# LCR.net
KiCad netlist of a schematic drawn in EasyEDA Pro
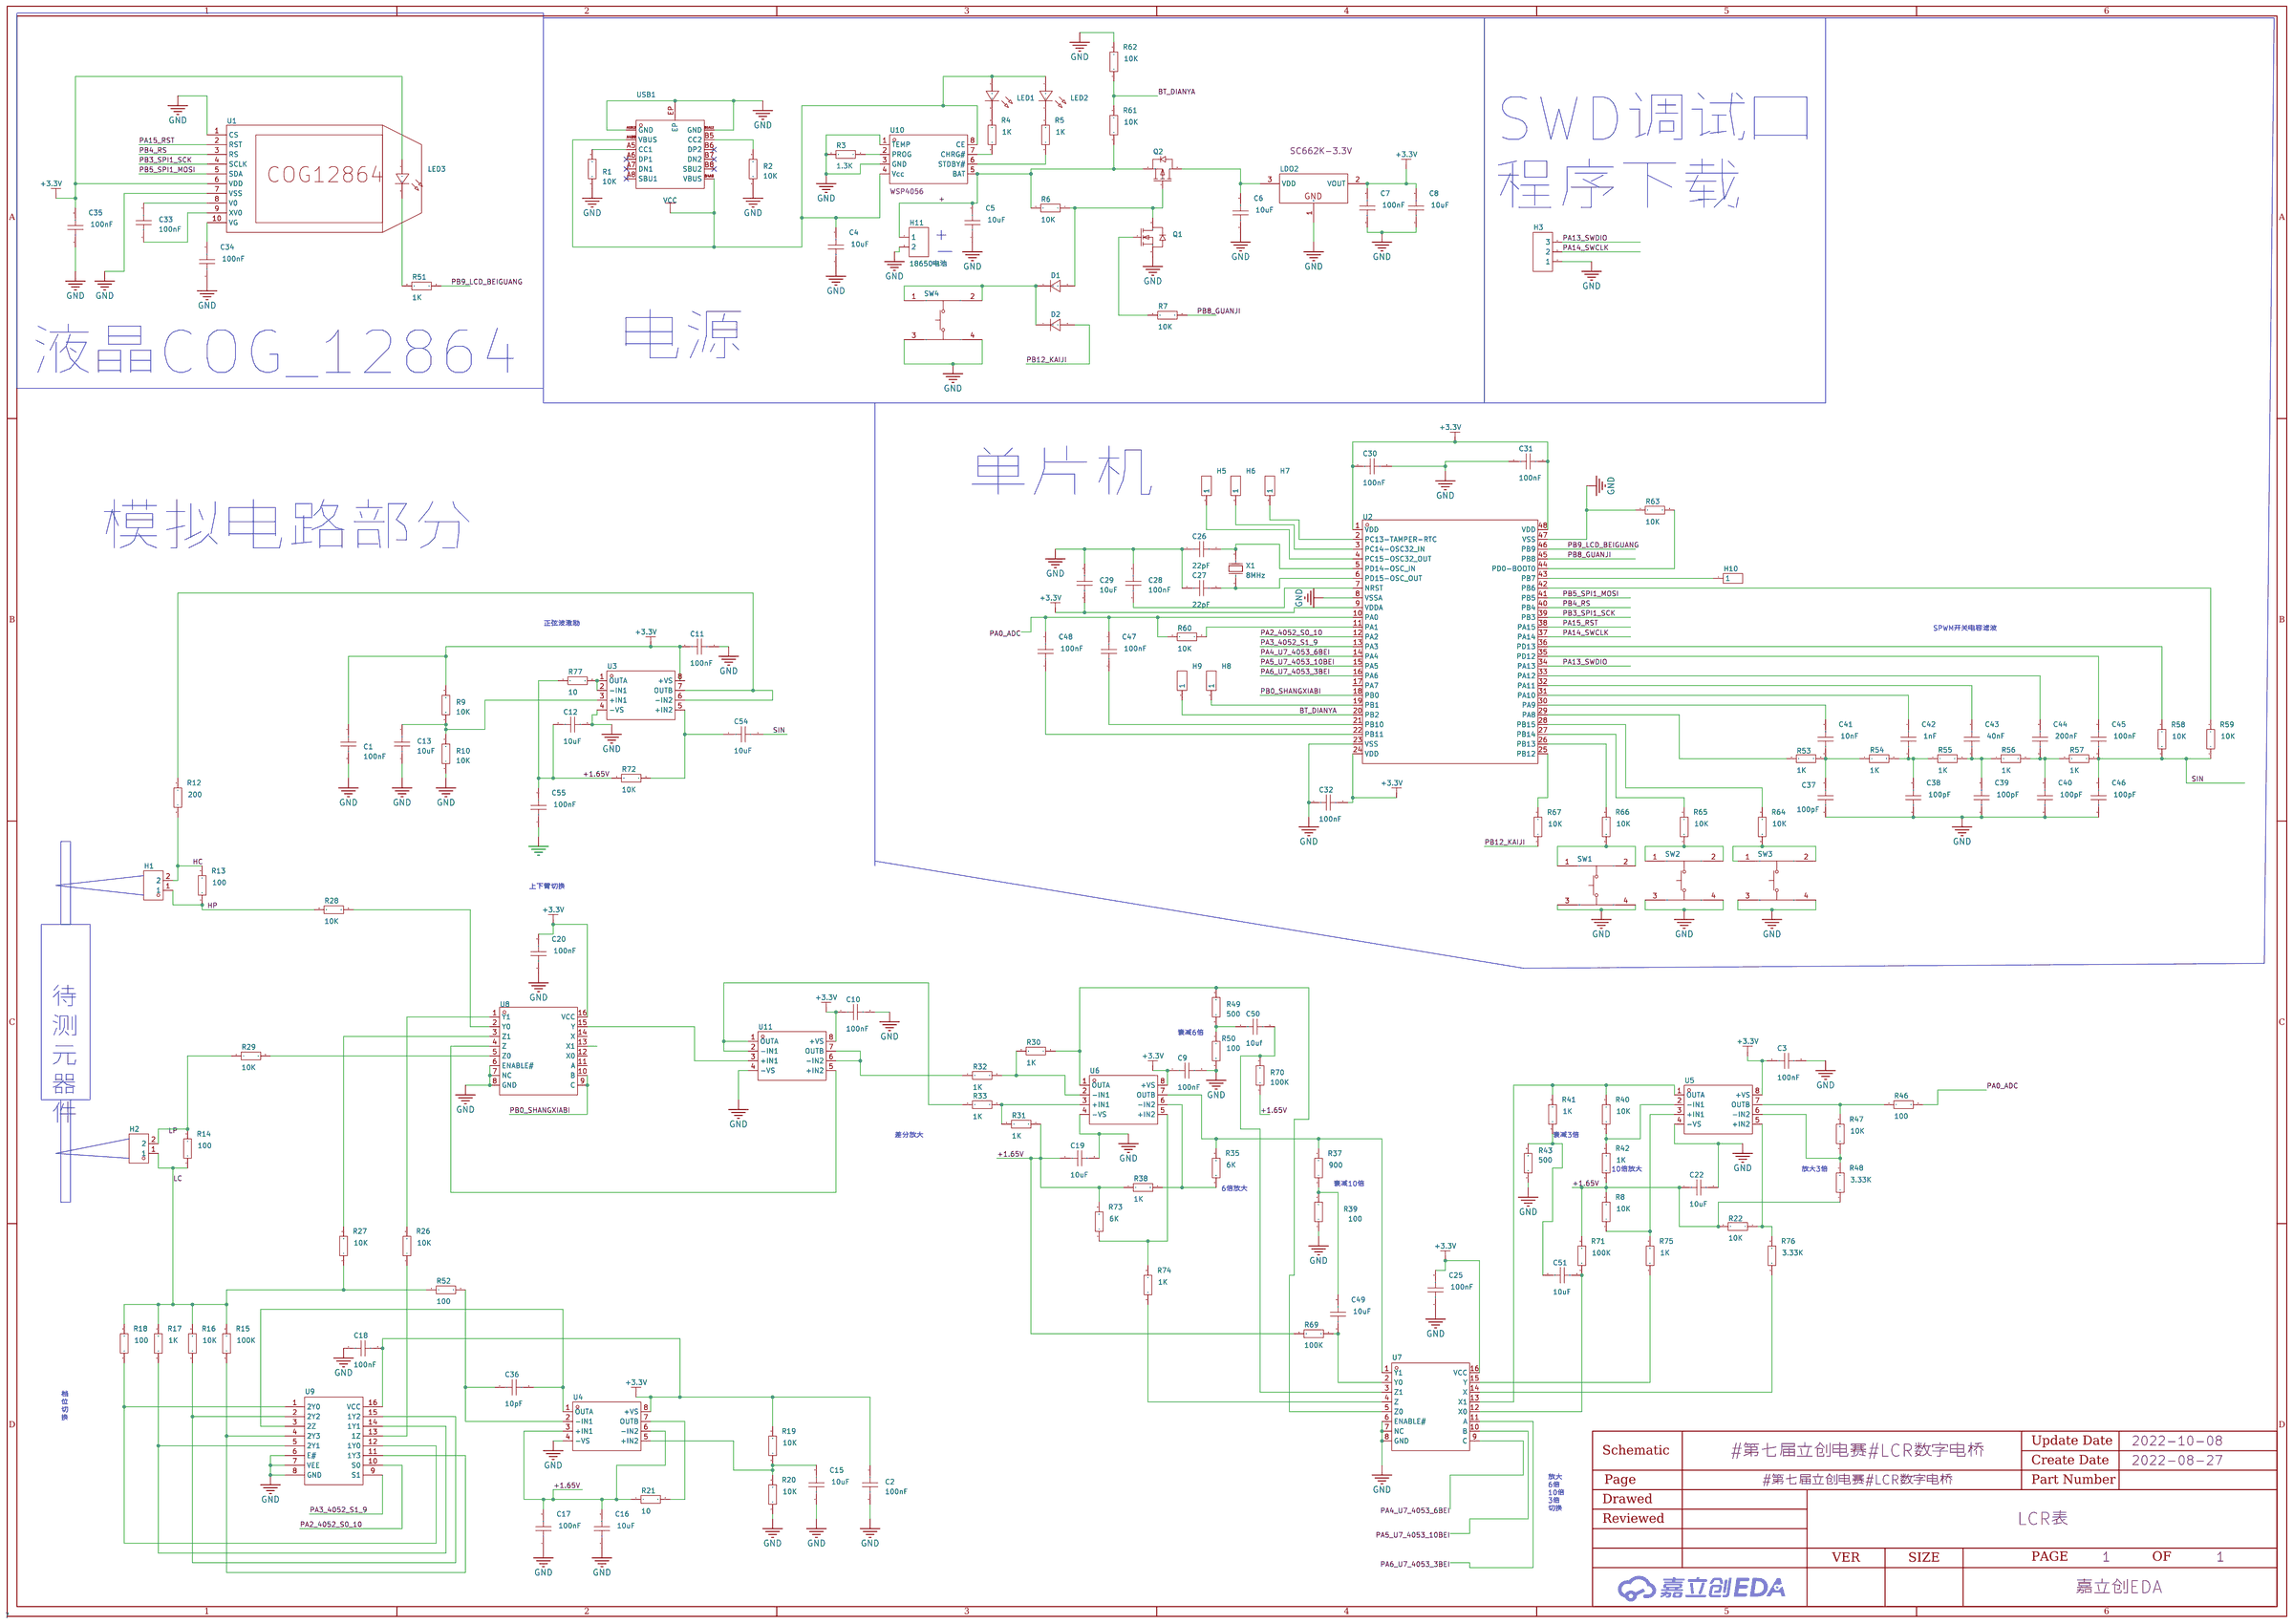
[diagram p0: schematic sheet]

(export (version "E")
  (design (tool "Eeschema 10.0.6"))
  (components
    (comp (ref "C1")
      (value "100nF")
      (footprint "easyedapro:C0603")
      (description "容值:100nF;精度:±10%;额定电压:50V;温度系数:X7R;")
      (libsource (lib "easyedapro") (part "C1210X7R475K630NT"))
    )
    (comp (ref "C2")
      (value "100nF")
      (footprint "easyedapro:C0603")
      (description "容值:100nF;精度:±10%;额定电压:50V;温度系数:X7R;")
      (libsource (lib "easyedapro") (part "C1210X7R475K630NT"))
    )
    (comp (ref "C3")
      (value "100nF")
      (footprint "easyedapro:C0603")
      (description "容值:100nF;精度:±10%;额定电压:50V;温度系数:X7R;")
      (libsource (lib "easyedapro") (part "C1210X7R475K630NT"))
    )
    (comp (ref "C4")
      (value "10uF")
      (footprint "easyedapro:C0603")
      (description "容值:100nF;精度:±10%;额定电压:50V;温度系数:X7R;")
      (libsource (lib "easyedapro") (part "C1210X7R475K630NT"))
    )
    (comp (ref "C5")
      (value "10uF")
      (footprint "easyedapro:C0603")
      (description "容值:100nF;精度:±10%;额定电压:50V;温度系数:X7R;")
      (libsource (lib "easyedapro") (part "C1210X7R475K630NT"))
    )
    (comp (ref "C6")
      (value "10uF")
      (footprint "easyedapro:C0603")
      (description "容值:100nF;精度:±10%;额定电压:50V;温度系数:X7R;")
      (libsource (lib "easyedapro") (part "C1210X7R475K630NT"))
    )
    (comp (ref "C7")
      (value "100nF")
      (footprint "easyedapro:C0603")
      (description "容值:100nF;精度:±10%;额定电压:50V;温度系数:X7R;")
      (libsource (lib "easyedapro") (part "C1210X7R475K630NT"))
    )
    (comp (ref "C8")
      (value "10uF")
      (footprint "easyedapro:C0603")
      (description "容值:100nF;精度:±10%;额定电压:50V;温度系数:X7R;")
      (libsource (lib "easyedapro") (part "C1210X7R475K630NT"))
    )
    (comp (ref "C9")
      (value "100nF")
      (footprint "easyedapro:C0603")
      (description "容值:100nF;精度:±10%;额定电压:50V;温度系数:X7R;")
      (libsource (lib "easyedapro") (part "C1210X7R475K630NT"))
    )
    (comp (ref "C10")
      (value "100nF")
      (footprint "easyedapro:C0603")
      (description "容值:100nF;精度:±10%;额定电压:50V;温度系数:X7R;")
      (libsource (lib "easyedapro") (part "C1210X7R475K630NT"))
    )
    (comp (ref "C11")
      (value "100nF")
      (footprint "easyedapro:C0603")
      (description "容值:100nF;精度:±10%;额定电压:50V;温度系数:X7R;")
      (libsource (lib "easyedapro") (part "C1210X7R475K630NT"))
    )
    (comp (ref "C12")
      (value "10uF")
      (footprint "easyedapro:C0603")
      (description "容值:100nF;精度:±10%;额定电压:50V;温度系数:X7R;")
      (libsource (lib "easyedapro") (part "C1210X7R475K630NT"))
    )
    (comp (ref "C13")
      (value "10uF")
      (footprint "easyedapro:C0603")
      (description "容值:100nF;精度:±10%;额定电压:50V;温度系数:X7R;")
      (libsource (lib "easyedapro") (part "C1210X7R475K630NT"))
    )
    (comp (ref "C15")
      (value "10uF")
      (footprint "easyedapro:C0603")
      (description "容值:100nF;精度:±10%;额定电压:50V;温度系数:X7R;")
      (libsource (lib "easyedapro") (part "C1210X7R475K630NT"))
    )
    (comp (ref "C16")
      (value "10uF")
      (footprint "easyedapro:C0603")
      (description "容值:100nF;精度:±10%;额定电压:50V;温度系数:X7R;")
      (libsource (lib "easyedapro") (part "C1210X7R475K630NT"))
    )
    (comp (ref "C17")
      (value "100nF")
      (footprint "easyedapro:C0603")
      (description "容值:100nF;精度:±10%;额定电压:50V;温度系数:X7R;")
      (libsource (lib "easyedapro") (part "C1210X7R475K630NT"))
    )
    (comp (ref "C18")
      (value "100nF")
      (footprint "easyedapro:C0603")
      (description "容值:100nF;精度:±10%;额定电压:50V;温度系数:X7R;")
      (libsource (lib "easyedapro") (part "C1210X7R475K630NT"))
    )
    (comp (ref "C19")
      (value "10uF")
      (footprint "easyedapro:C0603")
      (description "容值:100nF;精度:±10%;额定电压:50V;温度系数:X7R;")
      (libsource (lib "easyedapro") (part "C1210X7R475K630NT"))
    )
    (comp (ref "C20")
      (value "100nF")
      (footprint "easyedapro:C0603")
      (description "容值:100nF;精度:±10%;额定电压:50V;温度系数:X7R;")
      (libsource (lib "easyedapro") (part "C1210X7R475K630NT"))
    )
    (comp (ref "C22")
      (value "10uF")
      (footprint "easyedapro:C0603")
      (description "容值:100nF;精度:±10%;额定电压:50V;温度系数:X7R;")
      (libsource (lib "easyedapro") (part "C1210X7R475K630NT"))
    )
    (comp (ref "C25")
      (value "100nF")
      (footprint "easyedapro:C0603")
      (description "容值:100nF;精度:±10%;额定电压:50V;温度系数:X7R;")
      (libsource (lib "easyedapro") (part "C1210X7R475K630NT"))
    )
    (comp (ref "C26")
      (value "22pF")
      (footprint "easyedapro:C0603")
      (description "容值:100nF;精度:±10%;额定电压:50V;温度系数:X7R;")
      (libsource (lib "easyedapro") (part "C1210X7R475K630NT"))
    )
    (comp (ref "C27")
      (value "22pF")
      (footprint "easyedapro:C0603")
      (description "容值:100nF;精度:±10%;额定电压:50V;温度系数:X7R;")
      (libsource (lib "easyedapro") (part "C1210X7R475K630NT"))
    )
    (comp (ref "C28")
      (value "100nF")
      (footprint "easyedapro:C0603")
      (description "容值:100nF;精度:±10%;额定电压:50V;温度系数:X7R;")
      (libsource (lib "easyedapro") (part "C1210X7R475K630NT"))
    )
    (comp (ref "C29")
      (value "10uF")
      (footprint "easyedapro:C0603")
      (description "容值:100nF;精度:±10%;额定电压:50V;温度系数:X7R;")
      (libsource (lib "easyedapro") (part "C1210X7R475K630NT"))
    )
    (comp (ref "C30")
      (value "100nF")
      (footprint "easyedapro:C0603")
      (description "容值:100nF;精度:±10%;额定电压:50V;温度系数:X7R;")
      (libsource (lib "easyedapro") (part "C1210X7R475K630NT"))
    )
    (comp (ref "C31")
      (value "100nF")
      (footprint "easyedapro:C0603")
      (description "容值:100nF;精度:±10%;额定电压:50V;温度系数:X7R;")
      (libsource (lib "easyedapro") (part "C1210X7R475K630NT"))
    )
    (comp (ref "C32")
      (value "100nF")
      (footprint "easyedapro:C0603")
      (description "容值:100nF;精度:±10%;额定电压:50V;温度系数:X7R;")
      (libsource (lib "easyedapro") (part "C1210X7R475K630NT"))
    )
    (comp (ref "C33")
      (value "100nF")
      (footprint "easyedapro:C0603")
      (description "容值:100nF;精度:±10%;额定电压:50V;温度系数:X7R;")
      (libsource (lib "easyedapro") (part "C1210X7R475K630NT"))
    )
    (comp (ref "C34")
      (value "100nF")
      (footprint "easyedapro:C0603")
      (description "容值:100nF;精度:±10%;额定电压:50V;温度系数:X7R;")
      (libsource (lib "easyedapro") (part "C1210X7R475K630NT"))
    )
    (comp (ref "C35")
      (value "100nF")
      (footprint "easyedapro:C0603")
      (description "容值:100nF;精度:±10%;额定电压:50V;温度系数:X7R;")
      (libsource (lib "easyedapro") (part "C1210X7R475K630NT"))
    )
    (comp (ref "C36")
      (value "10pF")
      (footprint "easyedapro:C0603")
      (description "容值:100nF;精度:±10%;额定电压:50V;温度系数:X7R;")
      (libsource (lib "easyedapro") (part "C1210X7R475K630NT"))
    )
    (comp (ref "C37")
      (value "100pF")
      (footprint "easyedapro:C0603")
      (description "容值:100nF;精度:±10%;额定电压:50V;温度系数:X7R;")
      (libsource (lib "easyedapro") (part "C1210X7R475K630NT"))
    )
    (comp (ref "C38")
      (value "100pF")
      (footprint "easyedapro:C0603")
      (description "容值:100nF;精度:±10%;额定电压:50V;温度系数:X7R;")
      (libsource (lib "easyedapro") (part "C1210X7R475K630NT"))
    )
    (comp (ref "C39")
      (value "100pF")
      (footprint "easyedapro:C0603")
      (description "容值:100nF;精度:±10%;额定电压:50V;温度系数:X7R;")
      (libsource (lib "easyedapro") (part "C1210X7R475K630NT"))
    )
    (comp (ref "C40")
      (value "100pF")
      (footprint "easyedapro:C0603")
      (description "容值:100nF;精度:±10%;额定电压:50V;温度系数:X7R;")
      (libsource (lib "easyedapro") (part "C1210X7R475K630NT"))
    )
    (comp (ref "C41")
      (value "10nF")
      (footprint "easyedapro:C0603")
      (description "容值:100nF;精度:±10%;额定电压:50V;温度系数:X7R;")
      (libsource (lib "easyedapro") (part "C1210X7R475K630NT"))
    )
    (comp (ref "C42")
      (value "1nF")
      (footprint "easyedapro:C0603")
      (description "容值:100nF;精度:±10%;额定电压:50V;温度系数:X7R;")
      (libsource (lib "easyedapro") (part "C1210X7R475K630NT"))
    )
    (comp (ref "C43")
      (value "40nF")
      (footprint "easyedapro:C0603")
      (description "容值:100nF;精度:±10%;额定电压:50V;温度系数:X7R;")
      (libsource (lib "easyedapro") (part "C1210X7R475K630NT"))
    )
    (comp (ref "C44")
      (value "200nF")
      (footprint "easyedapro:C0603")
      (description "容值:100nF;精度:±10%;额定电压:50V;温度系数:X7R;")
      (libsource (lib "easyedapro") (part "C1210X7R475K630NT"))
    )
    (comp (ref "C45")
      (value "100nF")
      (footprint "easyedapro:C0603")
      (description "容值:100nF;精度:±10%;额定电压:50V;温度系数:X7R;")
      (libsource (lib "easyedapro") (part "C1210X7R475K630NT"))
    )
    (comp (ref "C46")
      (value "100pF")
      (footprint "easyedapro:C0603")
      (description "容值:100nF;精度:±10%;额定电压:50V;温度系数:X7R;")
      (libsource (lib "easyedapro") (part "C1210X7R475K630NT"))
    )
    (comp (ref "C47")
      (value "100nF")
      (footprint "easyedapro:C0603")
      (description "容值:100nF;精度:±10%;额定电压:50V;温度系数:X7R;")
      (libsource (lib "easyedapro") (part "C1210X7R475K630NT"))
    )
    (comp (ref "C48")
      (value "100nF")
      (footprint "easyedapro:C0603")
      (description "容值:100nF;精度:±10%;额定电压:50V;温度系数:X7R;")
      (libsource (lib "easyedapro") (part "C1210X7R475K630NT"))
    )
    (comp (ref "C49")
      (value "10uF")
      (footprint "easyedapro:C0603")
      (description "容值:100nF;精度:±10%;额定电压:50V;温度系数:X7R;")
      (libsource (lib "easyedapro") (part "C1210X7R475K630NT"))
    )
    (comp (ref "C50")
      (value "10uf")
      (footprint "easyedapro:C0603")
      (description "容值:100nF;精度:±10%;额定电压:50V;温度系数:X7R;")
      (libsource (lib "easyedapro") (part "C1210X7R475K630NT"))
    )
    (comp (ref "C51")
      (value "10uF")
      (footprint "easyedapro:C0603")
      (description "容值:100nF;精度:±10%;额定电压:50V;温度系数:X7R;")
      (libsource (lib "easyedapro") (part "C1210X7R475K630NT"))
    )
    (comp (ref "C54")
      (value "10uF")
      (footprint "easyedapro:C0603")
      (description "容值:100nF;精度:±10%;额定电压:50V;温度系数:X7R;")
      (libsource (lib "easyedapro") (part "C1210X7R475K630NT"))
    )
    (comp (ref "C55")
      (value "100nF")
      (footprint "easyedapro:C0603")
      (description "容值:100nF;精度:±10%;额定电压:50V;温度系数:X7R;")
      (libsource (lib "easyedapro") (part "C1210X7R475K630NT"))
    )
    (comp (ref "D1")
      (value "1N4148")
      (footprint "easyedapro:DO-35_BD2.0-L4.2-P8.20-D0.5-RD")
      (fields (field (name "Manufacturer") "GOOD-ARK(固锝)"))
      (libsource (lib "easyedapro") (part "1N4148_C406389"))
    )
    (comp (ref "D2")
      (value "1N4148")
      (footprint "easyedapro:DO-35_BD2.0-L4.2-P8.20-D0.5-RD")
      (fields (field (name "Manufacturer") "GOOD-ARK(固锝)"))
      (libsource (lib "easyedapro") (part "1N4148_C406389"))
    )
    (comp (ref "H1")
      (value "PZ254V-11-02P")
      (footprint "easyedapro:HDR-TH_2P-P2.54-V-M")
      (fields (field (name "Manufacturer") "XFCN(兴飞)"))
      (libsource (lib "easyedapro") (part "PZ254V-11-02P"))
    )
    (comp (ref "H2")
      (value "PZ254V-11-02P")
      (footprint "easyedapro:HDR-TH_2P-P2.54-V-M")
      (fields (field (name "Manufacturer") "XFCN(兴飞)"))
      (libsource (lib "easyedapro") (part "PZ254V-11-02P"))
    )
    (comp (ref "H3")
      (value "2.54-1*3P针")
      (footprint "easyedapro:HDR-TH_3P-P2.54-V-M-1")
      (fields (field (name "Manufacturer") "BOOMELE(博穆精密)"))
      (libsource (lib "easyedapro") (part "Header-Male-2.54_1x3"))
    )
    (comp (ref "H5")
      (value "~")
      (footprint "easyedapro:HDR-TH_1P-V-M_XKB_X4611WV-01I-C28D40")
      (libsource (lib "easyedapro") (part "HDR_1x1"))
    )
    (comp (ref "H6")
      (value "~")
      (footprint "easyedapro:HDR-TH_1P-V-M_XKB_X4611WV-01I-C28D40")
      (libsource (lib "easyedapro") (part "HDR_1x1"))
    )
    (comp (ref "H7")
      (value "~")
      (footprint "easyedapro:HDR-TH_1P-V-M_XKB_X4611WV-01I-C28D40")
      (libsource (lib "easyedapro") (part "HDR_1x1"))
    )
    (comp (ref "H8")
      (value "~")
      (footprint "easyedapro:HDR-TH_1P-V-M_XKB_X4611WV-01I-C28D40")
      (libsource (lib "easyedapro") (part "HDR_1x1"))
    )
    (comp (ref "H9")
      (value "~")
      (footprint "easyedapro:HDR-TH_1P-V-M_XKB_X4611WV-01I-C28D40")
      (libsource (lib "easyedapro") (part "HDR_1x1"))
    )
    (comp (ref "H10")
      (value "~")
      (footprint "easyedapro:HDR-TH_1P-V-M_XKB_X4611WV-01I-C28D40")
      (libsource (lib "easyedapro") (part "HDR_1x1"))
    )
    (comp (ref "H11")
      (value "18650电池")
      (footprint "easyedapro:HDR-TH_2P-P2.54-V-F")
      (libsource (lib "easyedapro") (part "Header-Female-2.54_1x2"))
    )
    (comp (ref "LDO2")
      (value "SC662K-3.3V")
      (footprint "easyedapro:SOT-23-3_L2.9-W1.3-P1.90-LS2.4-BR")
      (description "输出类型:固定;输出极性:正;输出通道数:1;最大输入电压:6V;输出电压:3.3V;压差:38mV@(10mA);输出电流:250mA;电源纹波抑制比(PRSS):50dB@(1kHz);")
      (fields (field (name "Manufacturer Part") "SC662K-3.3V") (field (name "Manufacturer") "FM富满"))
      (libsource (lib "easyedapro") (part "SC662K-3.3V"))
    )
    (comp (ref "LED1")
      (value "~")
      (footprint "easyedapro:LED-TH_BD3.0-P2.54-FD")
      (libsource (lib "easyedapro") (part "LED_TH-R"))
    )
    (comp (ref "LED2")
      (value "~")
      (footprint "easyedapro:LED-TH_BD3.0-P2.54-FD")
      (libsource (lib "easyedapro") (part "LED_TH-R"))
    )
    (comp (ref "LED3")
      (value "~")
      (footprint "easyedapro:LED-TH_BD3.0-P2.54-FD")
      (libsource (lib "easyedapro") (part "LED_TH-R"))
    )
    (comp (ref "Q1")
      (value "AO3400A")
      (footprint "easyedapro:SOT-23-3_L2.9-W1.3-P1.90-LS2.4-BR")
      (fields (field (name "Manufacturer") "UMW(友台半导体)"))
      (libsource (lib "easyedapro") (part "AO3400A_C347475"))
    )
    (comp (ref "Q2")
      (value "AO3401A")
      (footprint "easyedapro:SOT-23_L2.9-W1.3-P1.90-LS2.4-BR")
      (fields (field (name "Manufacturer") "UMW(友台半导体)"))
      (libsource (lib "easyedapro") (part "AO3401A_C347476"))
    )
    (comp (ref "R1")
      (value "10K")
      (footprint "easyedapro:R1206")
      (fields (field (name "Manufacturer Part") "RK73H2ETTD1002F") (field (name "Manufacturer") "KOA"))
      (libsource (lib "easyedapro") (part "电阻"))
    )
    (comp (ref "R2")
      (value "10K")
      (footprint "easyedapro:R1206")
      (fields (field (name "Manufacturer Part") "RK73H2ETTD1002F") (field (name "Manufacturer") "KOA"))
      (libsource (lib "easyedapro") (part "电阻"))
    )
    (comp (ref "R3")
      (value "1.3K")
      (footprint "easyedapro:R1206")
      (fields (field (name "Manufacturer Part") "RK73H2ETTD1002F") (field (name "Manufacturer") "KOA"))
      (libsource (lib "easyedapro") (part "电阻"))
    )
    (comp (ref "R4")
      (value "1K")
      (footprint "easyedapro:R1206")
      (fields (field (name "Manufacturer Part") "RK73H2ETTD1002F") (field (name "Manufacturer") "KOA"))
      (libsource (lib "easyedapro") (part "电阻"))
    )
    (comp (ref "R5")
      (value "1K")
      (footprint "easyedapro:R1206")
      (fields (field (name "Manufacturer Part") "RK73H2ETTD1002F") (field (name "Manufacturer") "KOA"))
      (libsource (lib "easyedapro") (part "电阻"))
    )
    (comp (ref "R6")
      (value "10K")
      (footprint "easyedapro:R1206")
      (fields (field (name "Manufacturer Part") "RK73H2ETTD1002F") (field (name "Manufacturer") "KOA"))
      (libsource (lib "easyedapro") (part "电阻"))
    )
    (comp (ref "R7")
      (value "10K")
      (footprint "easyedapro:R1206")
      (fields (field (name "Manufacturer Part") "RK73H2ETTD1002F") (field (name "Manufacturer") "KOA"))
      (libsource (lib "easyedapro") (part "电阻"))
    )
    (comp (ref "R8")
      (value "10K")
      (footprint "easyedapro:R1206")
      (fields (field (name "Manufacturer Part") "RK73H2ETTD1002F") (field (name "Manufacturer") "KOA"))
      (libsource (lib "easyedapro") (part "电阻"))
    )
    (comp (ref "R9")
      (value "10K")
      (footprint "easyedapro:R1206")
      (fields (field (name "Manufacturer Part") "RK73H2ETTD1002F") (field (name "Manufacturer") "KOA"))
      (libsource (lib "easyedapro") (part "电阻"))
    )
    (comp (ref "R10")
      (value "10K")
      (footprint "easyedapro:R1206")
      (fields (field (name "Manufacturer Part") "RK73H2ETTD1002F") (field (name "Manufacturer") "KOA"))
      (libsource (lib "easyedapro") (part "电阻"))
    )
    (comp (ref "R12")
      (value "200")
      (footprint "easyedapro:R1206")
      (fields (field (name "Manufacturer Part") "RK73H2ETTD1002F") (field (name "Manufacturer") "KOA"))
      (libsource (lib "easyedapro") (part "电阻"))
    )
    (comp (ref "R13")
      (value "100")
      (footprint "easyedapro:R1206")
      (fields (field (name "Manufacturer Part") "RK73H2ETTD1002F") (field (name "Manufacturer") "KOA"))
      (libsource (lib "easyedapro") (part "电阻"))
    )
    (comp (ref "R14")
      (value "100")
      (footprint "easyedapro:R1206")
      (fields (field (name "Manufacturer Part") "RK73H2ETTD1002F") (field (name "Manufacturer") "KOA"))
      (libsource (lib "easyedapro") (part "电阻"))
    )
    (comp (ref "R15")
      (value "100K")
      (footprint "easyedapro:R1206")
      (fields (field (name "Manufacturer Part") "RK73H2ETTD1002F") (field (name "Manufacturer") "KOA"))
      (libsource (lib "easyedapro") (part "电阻"))
    )
    (comp (ref "R16")
      (value "10K")
      (footprint "easyedapro:R1206")
      (fields (field (name "Manufacturer Part") "RK73H2ETTD1002F") (field (name "Manufacturer") "KOA"))
      (libsource (lib "easyedapro") (part "电阻"))
    )
    (comp (ref "R17")
      (value "1K")
      (footprint "easyedapro:R1206")
      (fields (field (name "Manufacturer Part") "RK73H2ETTD1002F") (field (name "Manufacturer") "KOA"))
      (libsource (lib "easyedapro") (part "电阻"))
    )
    (comp (ref "R18")
      (value "100")
      (footprint "easyedapro:R1206")
      (fields (field (name "Manufacturer Part") "RK73H2ETTD1002F") (field (name "Manufacturer") "KOA"))
      (libsource (lib "easyedapro") (part "电阻"))
    )
    (comp (ref "R19")
      (value "10K")
      (footprint "easyedapro:R1206")
      (fields (field (name "Manufacturer Part") "RK73H2ETTD1002F") (field (name "Manufacturer") "KOA"))
      (libsource (lib "easyedapro") (part "电阻"))
    )
    (comp (ref "R20")
      (value "10K")
      (footprint "easyedapro:R1206")
      (fields (field (name "Manufacturer Part") "RK73H2ETTD1002F") (field (name "Manufacturer") "KOA"))
      (libsource (lib "easyedapro") (part "电阻"))
    )
    (comp (ref "R21")
      (value "10")
      (footprint "easyedapro:R1206")
      (fields (field (name "Manufacturer Part") "RK73H2ETTD1002F") (field (name "Manufacturer") "KOA"))
      (libsource (lib "easyedapro") (part "电阻"))
    )
    (comp (ref "R22")
      (value "10K")
      (footprint "easyedapro:R1206")
      (fields (field (name "Manufacturer Part") "RK73H2ETTD1002F") (field (name "Manufacturer") "KOA"))
      (libsource (lib "easyedapro") (part "电阻"))
    )
    (comp (ref "R26")
      (value "10K")
      (footprint "easyedapro:R1206")
      (fields (field (name "Manufacturer Part") "RK73H2ETTD1002F") (field (name "Manufacturer") "KOA"))
      (libsource (lib "easyedapro") (part "电阻"))
    )
    (comp (ref "R27")
      (value "10K")
      (footprint "easyedapro:R1206")
      (fields (field (name "Manufacturer Part") "RK73H2ETTD1002F") (field (name "Manufacturer") "KOA"))
      (libsource (lib "easyedapro") (part "电阻"))
    )
    (comp (ref "R28")
      (value "10K")
      (footprint "easyedapro:R1206")
      (fields (field (name "Manufacturer Part") "RK73H2ETTD1002F") (field (name "Manufacturer") "KOA"))
      (libsource (lib "easyedapro") (part "电阻"))
    )
    (comp (ref "R29")
      (value "10K")
      (footprint "easyedapro:R1206")
      (fields (field (name "Manufacturer Part") "RK73H2ETTD1002F") (field (name "Manufacturer") "KOA"))
      (libsource (lib "easyedapro") (part "电阻"))
    )
    (comp (ref "R30")
      (value "1K")
      (footprint "easyedapro:R1206")
      (fields (field (name "Manufacturer Part") "RK73H2ETTD1002F") (field (name "Manufacturer") "KOA"))
      (libsource (lib "easyedapro") (part "电阻"))
    )
    (comp (ref "R31")
      (value "1K")
      (footprint "easyedapro:R1206")
      (fields (field (name "Manufacturer Part") "RK73H2ETTD1002F") (field (name "Manufacturer") "KOA"))
      (libsource (lib "easyedapro") (part "电阻"))
    )
    (comp (ref "R32")
      (value "1K")
      (footprint "easyedapro:R1206")
      (fields (field (name "Manufacturer Part") "RK73H2ETTD1002F") (field (name "Manufacturer") "KOA"))
      (libsource (lib "easyedapro") (part "电阻"))
    )
    (comp (ref "R33")
      (value "1K")
      (footprint "easyedapro:R1206")
      (fields (field (name "Manufacturer Part") "RK73H2ETTD1002F") (field (name "Manufacturer") "KOA"))
      (libsource (lib "easyedapro") (part "电阻"))
    )
    (comp (ref "R35")
      (value "6K")
      (footprint "easyedapro:R1206")
      (fields (field (name "Manufacturer Part") "RK73H2ETTD1002F") (field (name "Manufacturer") "KOA"))
      (libsource (lib "easyedapro") (part "电阻"))
    )
    (comp (ref "R37")
      (value "900")
      (footprint "easyedapro:R1206")
      (fields (field (name "Manufacturer Part") "RK73H2ETTD1002F") (field (name "Manufacturer") "KOA"))
      (libsource (lib "easyedapro") (part "电阻"))
    )
    (comp (ref "R38")
      (value "1K")
      (footprint "easyedapro:R1206")
      (fields (field (name "Manufacturer Part") "RK73H2ETTD1002F") (field (name "Manufacturer") "KOA"))
      (libsource (lib "easyedapro") (part "电阻"))
    )
    (comp (ref "R39")
      (value "100")
      (footprint "easyedapro:R1206")
      (fields (field (name "Manufacturer Part") "RK73H2ETTD1002F") (field (name "Manufacturer") "KOA"))
      (libsource (lib "easyedapro") (part "电阻"))
    )
    (comp (ref "R40")
      (value "10K")
      (footprint "easyedapro:R1206")
      (fields (field (name "Manufacturer Part") "RK73H2ETTD1002F") (field (name "Manufacturer") "KOA"))
      (libsource (lib "easyedapro") (part "电阻"))
    )
    (comp (ref "R41")
      (value "1K")
      (footprint "easyedapro:R1206")
      (fields (field (name "Manufacturer Part") "RK73H2ETTD1002F") (field (name "Manufacturer") "KOA"))
      (libsource (lib "easyedapro") (part "电阻"))
    )
    (comp (ref "R42")
      (value "1K")
      (footprint "easyedapro:R1206")
      (fields (field (name "Manufacturer Part") "RK73H2ETTD1002F") (field (name "Manufacturer") "KOA"))
      (libsource (lib "easyedapro") (part "电阻"))
    )
    (comp (ref "R43")
      (value "500")
      (footprint "easyedapro:R1206")
      (fields (field (name "Manufacturer Part") "RK73H2ETTD1002F") (field (name "Manufacturer") "KOA"))
      (libsource (lib "easyedapro") (part "电阻"))
    )
    (comp (ref "R46")
      (value "100")
      (footprint "easyedapro:R1206")
      (fields (field (name "Manufacturer Part") "RK73H2ETTD1002F") (field (name "Manufacturer") "KOA"))
      (libsource (lib "easyedapro") (part "电阻"))
    )
    (comp (ref "R47")
      (value "10K")
      (footprint "easyedapro:R1206")
      (fields (field (name "Manufacturer Part") "RK73H2ETTD1002F") (field (name "Manufacturer") "KOA"))
      (libsource (lib "easyedapro") (part "电阻"))
    )
    (comp (ref "R48")
      (value "3.33K")
      (footprint "easyedapro:R1206")
      (fields (field (name "Manufacturer Part") "RK73H2ETTD1002F") (field (name "Manufacturer") "KOA"))
      (libsource (lib "easyedapro") (part "电阻"))
    )
    (comp (ref "R49")
      (value "500")
      (footprint "easyedapro:R1206")
      (fields (field (name "Manufacturer Part") "RK73H2ETTD1002F") (field (name "Manufacturer") "KOA"))
      (libsource (lib "easyedapro") (part "电阻"))
    )
    (comp (ref "R50")
      (value "100")
      (footprint "easyedapro:R1206")
      (fields (field (name "Manufacturer Part") "RK73H2ETTD1002F") (field (name "Manufacturer") "KOA"))
      (libsource (lib "easyedapro") (part "电阻"))
    )
    (comp (ref "R51")
      (value "1K")
      (footprint "easyedapro:R1206")
      (fields (field (name "Manufacturer Part") "RK73H2ETTD1002F") (field (name "Manufacturer") "KOA"))
      (libsource (lib "easyedapro") (part "电阻"))
    )
    (comp (ref "R52")
      (value "100")
      (footprint "easyedapro:R1206")
      (fields (field (name "Manufacturer Part") "RK73H2ETTD1002F") (field (name "Manufacturer") "KOA"))
      (libsource (lib "easyedapro") (part "电阻"))
    )
    (comp (ref "R53")
      (value "1K")
      (footprint "easyedapro:R1206")
      (fields (field (name "Manufacturer Part") "RK73H2ETTD1002F") (field (name "Manufacturer") "KOA"))
      (libsource (lib "easyedapro") (part "电阻"))
    )
    (comp (ref "R54")
      (value "1K")
      (footprint "easyedapro:R1206")
      (fields (field (name "Manufacturer Part") "RK73H2ETTD1002F") (field (name "Manufacturer") "KOA"))
      (libsource (lib "easyedapro") (part "电阻"))
    )
    (comp (ref "R55")
      (value "1K")
      (footprint "easyedapro:R1206")
      (fields (field (name "Manufacturer Part") "RK73H2ETTD1002F") (field (name "Manufacturer") "KOA"))
      (libsource (lib "easyedapro") (part "电阻"))
    )
    (comp (ref "R56")
      (value "1K")
      (footprint "easyedapro:R1206")
      (fields (field (name "Manufacturer Part") "RK73H2ETTD1002F") (field (name "Manufacturer") "KOA"))
      (libsource (lib "easyedapro") (part "电阻"))
    )
    (comp (ref "R57")
      (value "1K")
      (footprint "easyedapro:R1206")
      (fields (field (name "Manufacturer Part") "RK73H2ETTD1002F") (field (name "Manufacturer") "KOA"))
      (libsource (lib "easyedapro") (part "电阻"))
    )
    (comp (ref "R58")
      (value "10K")
      (footprint "easyedapro:R1206")
      (fields (field (name "Manufacturer Part") "RK73H2ETTD1002F") (field (name "Manufacturer") "KOA"))
      (libsource (lib "easyedapro") (part "电阻"))
    )
    (comp (ref "R59")
      (value "10K")
      (footprint "easyedapro:R1206")
      (fields (field (name "Manufacturer Part") "RK73H2ETTD1002F") (field (name "Manufacturer") "KOA"))
      (libsource (lib "easyedapro") (part "电阻"))
    )
    (comp (ref "R60")
      (value "10K")
      (footprint "easyedapro:R1206")
      (fields (field (name "Manufacturer Part") "RK73H2ETTD1002F") (field (name "Manufacturer") "KOA"))
      (libsource (lib "easyedapro") (part "电阻"))
    )
    (comp (ref "R61")
      (value "10K")
      (footprint "easyedapro:R1206")
      (fields (field (name "Manufacturer Part") "RK73H2ETTD1002F") (field (name "Manufacturer") "KOA"))
      (libsource (lib "easyedapro") (part "电阻"))
    )
    (comp (ref "R62")
      (value "10K")
      (footprint "easyedapro:R1206")
      (fields (field (name "Manufacturer Part") "RK73H2ETTD1002F") (field (name "Manufacturer") "KOA"))
      (libsource (lib "easyedapro") (part "电阻"))
    )
    (comp (ref "R63")
      (value "10K")
      (footprint "easyedapro:R1206")
      (fields (field (name "Manufacturer Part") "RK73H2ETTD1002F") (field (name "Manufacturer") "KOA"))
      (libsource (lib "easyedapro") (part "电阻"))
    )
    (comp (ref "R64")
      (value "10K")
      (footprint "easyedapro:R1206")
      (fields (field (name "Manufacturer Part") "RK73H2ETTD1002F") (field (name "Manufacturer") "KOA"))
      (libsource (lib "easyedapro") (part "电阻"))
    )
    (comp (ref "R65")
      (value "10K")
      (footprint "easyedapro:R1206")
      (fields (field (name "Manufacturer Part") "RK73H2ETTD1002F") (field (name "Manufacturer") "KOA"))
      (libsource (lib "easyedapro") (part "电阻"))
    )
    (comp (ref "R66")
      (value "10K")
      (footprint "easyedapro:R1206")
      (fields (field (name "Manufacturer Part") "RK73H2ETTD1002F") (field (name "Manufacturer") "KOA"))
      (libsource (lib "easyedapro") (part "电阻"))
    )
    (comp (ref "R67")
      (value "10K")
      (footprint "easyedapro:R1206")
      (fields (field (name "Manufacturer Part") "RK73H2ETTD1002F") (field (name "Manufacturer") "KOA"))
      (libsource (lib "easyedapro") (part "电阻"))
    )
    (comp (ref "R69")
      (value "100K")
      (footprint "easyedapro:R1206")
      (fields (field (name "Manufacturer Part") "RK73H2ETTD1002F") (field (name "Manufacturer") "KOA"))
      (libsource (lib "easyedapro") (part "电阻"))
    )
    (comp (ref "R70")
      (value "100K")
      (footprint "easyedapro:R1206")
      (fields (field (name "Manufacturer Part") "RK73H2ETTD1002F") (field (name "Manufacturer") "KOA"))
      (libsource (lib "easyedapro") (part "电阻"))
    )
    (comp (ref "R71")
      (value "100K")
      (footprint "easyedapro:R1206")
      (fields (field (name "Manufacturer Part") "RK73H2ETTD1002F") (field (name "Manufacturer") "KOA"))
      (libsource (lib "easyedapro") (part "电阻"))
    )
    (comp (ref "R72")
      (value "10K")
      (footprint "easyedapro:R1206")
      (fields (field (name "Manufacturer Part") "RK73H2ETTD1002F") (field (name "Manufacturer") "KOA"))
      (libsource (lib "easyedapro") (part "电阻"))
    )
    (comp (ref "R73")
      (value "6K")
      (footprint "easyedapro:R1206")
      (fields (field (name "Manufacturer Part") "RK73H2ETTD1002F") (field (name "Manufacturer") "KOA"))
      (libsource (lib "easyedapro") (part "电阻"))
    )
    (comp (ref "R74")
      (value "1K")
      (footprint "easyedapro:R1206")
      (fields (field (name "Manufacturer Part") "RK73H2ETTD1002F") (field (name "Manufacturer") "KOA"))
      (libsource (lib "easyedapro") (part "电阻"))
    )
    (comp (ref "R75")
      (value "1K")
      (footprint "easyedapro:R1206")
      (fields (field (name "Manufacturer Part") "RK73H2ETTD1002F") (field (name "Manufacturer") "KOA"))
      (libsource (lib "easyedapro") (part "电阻"))
    )
    (comp (ref "R76")
      (value "3.33K")
      (footprint "easyedapro:R1206")
      (fields (field (name "Manufacturer Part") "RK73H2ETTD1002F") (field (name "Manufacturer") "KOA"))
      (libsource (lib "easyedapro") (part "电阻"))
    )
    (comp (ref "R77")
      (value "10")
      (footprint "easyedapro:R1206")
      (fields (field (name "Manufacturer Part") "RK73H2ETTD1002F") (field (name "Manufacturer") "KOA"))
      (libsource (lib "easyedapro") (part "电阻"))
    )
    (comp (ref "SW1")
      (value "TC-1109-C-B")
      (footprint "easyedapro:KEY-TH_4P-L4.5-W4.5-P3.00-LS5.8")
      (fields (field (name "Manufacturer") "XKB Connectivity(中国星坤)"))
      (libsource (lib "easyedapro") (part "TC-1109-C-B"))
    )
    (comp (ref "SW2")
      (value "TC-1109-C-B")
      (footprint "easyedapro:KEY-TH_4P-L4.5-W4.5-P3.00-LS5.8")
      (fields (field (name "Manufacturer") "XKB Connectivity(中国星坤)"))
      (libsource (lib "easyedapro") (part "TC-1109-C-B"))
    )
    (comp (ref "SW3")
      (value "TC-1109-C-B")
      (footprint "easyedapro:KEY-TH_4P-L4.5-W4.5-P3.00-LS5.8")
      (fields (field (name "Manufacturer") "XKB Connectivity(中国星坤)"))
      (libsource (lib "easyedapro") (part "TC-1109-C-B"))
    )
    (comp (ref "SW4")
      (value "TC-1109-C-B")
      (footprint "easyedapro:KEY-TH_4P-L4.5-W4.5-P3.00-LS5.8")
      (fields (field (name "Manufacturer") "XKB Connectivity(中国星坤)"))
      (libsource (lib "easyedapro") (part "TC-1109-C-B"))
    )
    (comp (ref "U1") (value "~") (libsource (lib "easyedapro") (part "COG12864")))
    (comp (ref "U2")
      (value "N32G430C8L7")
      (footprint "easyedapro:LQFP-48_L7.0-W7.0-P0.50-LS9.0-BL")
      (fields (field (name "Manufacturer") "Nations(国民技术)"))
      (libsource (lib "easyedapro") (part "N32G430C8L7"))
    )
    (comp (ref "U3")
      (value "COS722MR")
      (footprint "easyedapro:MSOP-8_L3.0-W3.0-P0.65-LS4.9-BL-1")
      (description "运放类型:低噪声运放;放大器组数:2;增益带宽积（GBP）:10MHz;压摆率（SR）:7.5 V/us;电源电压:2.1V ~ 5.5V;各通道供电电流:650uA;")
      (fields (field (name "Manufacturer") "COSINE(科山芯创)"))
      (libsource (lib "easyedapro") (part "COS722MR"))
    )
    (comp (ref "U4")
      (value "COS722MR")
      (footprint "easyedapro:MSOP-8_L3.0-W3.0-P0.65-LS4.9-BL-1")
      (description "运放类型:低噪声运放;放大器组数:2;增益带宽积（GBP）:10MHz;压摆率（SR）:7.5 V/us;电源电压:2.1V ~ 5.5V;各通道供电电流:650uA;")
      (fields (field (name "Manufacturer") "COSINE(科山芯创)"))
      (libsource (lib "easyedapro") (part "COS722MR"))
    )
    (comp (ref "U5")
      (value "COS722MR")
      (footprint "easyedapro:MSOP-8_L3.0-W3.0-P0.65-LS4.9-BL-1")
      (description "运放类型:低噪声运放;放大器组数:2;增益带宽积（GBP）:10MHz;压摆率（SR）:7.5 V/us;电源电压:2.1V ~ 5.5V;各通道供电电流:650uA;")
      (fields (field (name "Manufacturer") "COSINE(科山芯创)"))
      (libsource (lib "easyedapro") (part "COS722MR"))
    )
    (comp (ref "U6")
      (value "COS722MR")
      (footprint "easyedapro:MSOP-8_L3.0-W3.0-P0.65-LS4.9-BL-1")
      (description "运放类型:低噪声运放;放大器组数:2;增益带宽积（GBP）:10MHz;压摆率（SR）:7.5 V/us;电源电压:2.1V ~ 5.5V;各通道供电电流:650uA;")
      (fields (field (name "Manufacturer") "COSINE(科山芯创)"))
      (libsource (lib "easyedapro") (part "COS722MR"))
    )
    (comp (ref "U7")
      (value "RS2253XTSS16")
      (footprint "easyedapro:TSSOP-16_L5.0-W4.4-P0.65-LS6.4-BL")
      (description "开关电路:-;多路复用器/解复用器电路:-;导通电阻（最大值）:-;开关电压（最大值）:-;")
      (fields (field (name "Manufacturer") "RUNIC(润石)"))
      (libsource (lib "easyedapro") (part "RS2253XTSS16"))
    )
    (comp (ref "U8")
      (value "RS2253XTSS16")
      (footprint "easyedapro:TSSOP-16_L5.0-W4.4-P0.65-LS6.4-BL")
      (description "开关电路:-;多路复用器/解复用器电路:-;导通电阻（最大值）:-;开关电压（最大值）:-;")
      (fields (field (name "Manufacturer") "RUNIC(润石)"))
      (libsource (lib "easyedapro") (part "RS2253XTSS16"))
    )
    (comp (ref "U9")
      (value "74HC4052PW,118")
      (footprint "easyedapro:TSSOP-16_L5.0-W4.4-P0.65-LS6.4-BL")
      (fields (field (name "Manufacturer") "Nexperia(安世)"))
      (libsource (lib "easyedapro") (part "74HC4052PW,118"))
    )
    (comp (ref "U10")
      (value "WSP4056")
      (footprint "easyedapro:SOP-8_L5.1-W3.9-P1.27-LS6.0-BL")
      (fields (field (name "Manufacturer") "WINSOK(微硕)") (field (name "LCSC Part Name") "WSP4056"))
      (libsource (lib "easyedapro") (part "WSP4056"))
    )
    (comp (ref "U11")
      (value "COS722MR")
      (footprint "easyedapro:MSOP-8_L3.0-W3.0-P0.65-LS4.9-BL-1")
      (description "运放类型:低噪声运放;放大器组数:2;增益带宽积（GBP）:10MHz;压摆率（SR）:7.5 V/us;电源电压:2.1V ~ 5.5V;各通道供电电流:650uA;")
      (fields (field (name "Manufacturer") "COSINE(科山芯创)"))
      (libsource (lib "easyedapro") (part "COS722MR"))
    )
    (comp (ref "USB1")
      (value "TYPEC-304-ACP16")
      (footprint "easyedapro:USB-C-SMD_TYPE-C-16P-1")
      (description "连接器类型:Type-C;公母:母座;触点数量:16;端口数量:1;安装方式:卧贴;额定电流 - 电源:3A;工作温度范围:-40~+85;")
      (fields (field (name "Manufacturer") "XUNPU(讯普)"))
      (libsource (lib "easyedapro") (part "TYPEC-304-ACP16"))
    )
    (comp (ref "X1")
      (value "8MHz")
      (footprint "easyedapro:OSC-TH_L10.0-W4.5-P5.00")
      (description "晶振类型:49S晶振;频率:8MHz;频率公差:±20ppm;频率稳定度:±30ppm;负载电容:20pF;工作温度:-20~+70;")
      (fields (field (name "Manufacturer Part") "X49SD8MSD2SC") (field (name "Manufacturer") "YXC(扬兴科技)"))
      (libsource (lib "easyedapro") (part "X49SD8MSD2SC"))
    )
  )
  (nets
    (net (code "1") (name "+3.3V") (class "Default")
      (node (ref "C1") (pin "1") (pinfunction "1_1") (pintype "input"))
      (node (ref "C10") (pin "1") (pinfunction "1_1") (pintype "input"))
      (node (ref "C11") (pin "1") (pinfunction "1_1") (pintype "input"))
      (node (ref "C18") (pin "2") (pinfunction "2_2") (pintype "input"))
      (node (ref "C2") (pin "1") (pinfunction "1_1") (pintype "input"))
      (node (ref "C20") (pin "2") (pinfunction "2_2") (pintype "input"))
      (node (ref "C25") (pin "2") (pinfunction "2_2") (pintype "input"))
      (node (ref "C29") (pin "1") (pinfunction "1_1") (pintype "input"))
      (node (ref "C3") (pin "1") (pinfunction "1_1") (pintype "input"))
      (node (ref "C30") (pin "1") (pinfunction "1_1") (pintype "input"))
      (node (ref "C31") (pin "2") (pinfunction "2_2") (pintype "input"))
      (node (ref "C32") (pin "2") (pinfunction "2_2") (pintype "input"))
      (node (ref "C35") (pin "2") (pinfunction "2_2") (pintype "input"))
      (node (ref "C7") (pin "2") (pinfunction "2_2") (pintype "input"))
      (node (ref "C8") (pin "2") (pinfunction "2_2") (pintype "input"))
      (node (ref "C9") (pin "1") (pinfunction "1_1") (pintype "input"))
      (node (ref "LDO2") (pin "2") (pinfunction "VOUT_2") (pintype "input"))
      (node (ref "LED3") (pin "1") (pinfunction "C_1") (pintype "input"))
      (node (ref "R19") (pin "2") (pinfunction "2_2") (pintype "input"))
      (node (ref "R9") (pin "2") (pinfunction "2_2") (pintype "input"))
      (node (ref "U1") (pin "6") (pinfunction "VDD_6") (pintype "input"))
      (node (ref "U11") (pin "8") (pinfunction "+VS_8") (pintype "input"))
      (node (ref "U2") (pin "1") (pinfunction "VDD_1") (pintype "input"))
      (node (ref "U2") (pin "24") (pinfunction "VDD_24") (pintype "input"))
      (node (ref "U2") (pin "48") (pinfunction "VDD_48") (pintype "input"))
      (node (ref "U2") (pin "9") (pinfunction "VDDA_9") (pintype "input"))
      (node (ref "U3") (pin "8") (pinfunction "+VS_8") (pintype "input"))
      (node (ref "U4") (pin "8") (pinfunction "+VS_8") (pintype "input"))
      (node (ref "U5") (pin "8") (pinfunction "+VS_8") (pintype "input"))
      (node (ref "U6") (pin "8") (pinfunction "+VS_8") (pintype "input"))
      (node (ref "U7") (pin "16") (pinfunction "VCC_16") (pintype "input"))
      (node (ref "U8") (pin "16") (pinfunction "VCC_16") (pintype "input"))
      (node (ref "U9") (pin "16") (pinfunction "VCC_16") (pintype "input"))
    )
    (net (code "2") (name "/+") (class "Default")
      (node (ref "C5") (pin "2") (pinfunction "2_2") (pintype "input"))
      (node (ref "H11") (pin "1") (pinfunction "1_1") (pintype "input"))
      (node (ref "Q2") (pin "2") (pinfunction "S_2") (pintype "input"))
      (node (ref "R6") (pin "2") (pinfunction "2_2") (pintype "input"))
      (node (ref "R61") (pin "1") (pinfunction "1_1") (pintype "input"))
      (node (ref "U10") (pin "5") (pinfunction "BAT_5") (pintype "input"))
    )
    (net (code "3") (name "/+1.65V") (class "Default")
      (node (ref "C12") (pin "1") (pinfunction "1_1") (pintype "input"))
      (node (ref "C16") (pin "2") (pinfunction "2_2") (pintype "input"))
      (node (ref "C17") (pin "2") (pinfunction "2_2") (pintype "input"))
      (node (ref "C19") (pin "1") (pinfunction "1_1") (pintype "input"))
      (node (ref "C22") (pin "1") (pinfunction "1_1") (pintype "input"))
      (node (ref "C55") (pin "2") (pinfunction "2_2") (pintype "input"))
      (node (ref "R21") (pin "1") (pinfunction "1_1") (pintype "input"))
      (node (ref "R22") (pin "2") (pinfunction "2_2") (pintype "input"))
      (node (ref "R31") (pin "1") (pinfunction "1_1") (pintype "input"))
      (node (ref "R38") (pin "1") (pinfunction "1_1") (pintype "input"))
      (node (ref "R42") (pin "1") (pinfunction "1_1") (pintype "input"))
      (node (ref "R48") (pin "1") (pinfunction "1_1") (pintype "input"))
      (node (ref "R69") (pin "1") (pinfunction "1_1") (pintype "input"))
      (node (ref "R70") (pin "1") (pinfunction "1_1") (pintype "input"))
      (node (ref "R71") (pin "2") (pinfunction "2_2") (pintype "input"))
      (node (ref "R72") (pin "1") (pinfunction "1_1") (pintype "input"))
      (node (ref "R73") (pin "2") (pinfunction "2_2") (pintype "input"))
      (node (ref "R77") (pin "1") (pinfunction "1_1") (pintype "input"))
      (node (ref "R8") (pin "2") (pinfunction "2_2") (pintype "input"))
      (node (ref "U4") (pin "3") (pinfunction "+IN1_3") (pintype "input"))
      (node (ref "U4") (pin "6") (pinfunction "-IN2_6") (pintype "input"))
    )
    (net (code "4") (name "/BT_DIANYA") (class "Default")
      (node (ref "H9") (pin "1") (pinfunction "1_1") (pintype "unspecified"))
      (node (ref "R61") (pin "2") (pinfunction "2_2") (pintype "input"))
      (node (ref "R62") (pin "1") (pinfunction "1_1") (pintype "input"))
      (node (ref "U2") (pin "20") (pinfunction "PB2_20") (pintype "input"))
    )
    (net (code "5") (name "/HC") (class "Default")
      (node (ref "H1") (pin "2") (pinfunction "2_2") (pintype "input"))
      (node (ref "R12") (pin "1") (pinfunction "1_1") (pintype "input"))
      (node (ref "R13") (pin "2") (pinfunction "2_2") (pintype "input"))
    )
    (net (code "6") (name "/HP") (class "Default")
      (node (ref "H1") (pin "1") (pinfunction "1_1") (pintype "input"))
      (node (ref "R13") (pin "1") (pinfunction "1_1") (pintype "input"))
      (node (ref "R28") (pin "1") (pinfunction "1_1") (pintype "input"))
    )
    (net (code "7") (name "/LC") (class "Default")
      (node (ref "H2") (pin "1") (pinfunction "1_1") (pintype "input"))
      (node (ref "R14") (pin "1") (pinfunction "1_1") (pintype "input"))
      (node (ref "R15") (pin "2") (pinfunction "2_2") (pintype "input"))
      (node (ref "R16") (pin "2") (pinfunction "2_2") (pintype "input"))
      (node (ref "R17") (pin "2") (pinfunction "2_2") (pintype "input"))
      (node (ref "R18") (pin "2") (pinfunction "2_2") (pintype "input"))
      (node (ref "R27") (pin "1") (pinfunction "1_1") (pintype "input"))
      (node (ref "R52") (pin "1") (pinfunction "1_1") (pintype "input"))
    )
    (net (code "8") (name "/LP") (class "Default")
      (node (ref "H2") (pin "2") (pinfunction "2_2") (pintype "input"))
      (node (ref "R14") (pin "2") (pinfunction "2_2") (pintype "input"))
      (node (ref "R29") (pin "1") (pinfunction "1_1") (pintype "input"))
    )
    (net (code "9") (name "/PA0_ADC") (class "Default")
      (node (ref "C47") (pin "2") (pinfunction "2_2") (pintype "input"))
      (node (ref "C48") (pin "2") (pinfunction "2_2") (pintype "input"))
      (node (ref "R46") (pin "2") (pinfunction "2_2") (pintype "input"))
      (node (ref "R60") (pin "1") (pinfunction "1_1") (pintype "input"))
      (node (ref "U2") (pin "10") (pinfunction "PA0_10") (pintype "input"))
    )
    (net (code "10") (name "/PA2_4052_S0_10") (class "Default")
      (node (ref "U2") (pin "12") (pinfunction "PA2_12") (pintype "input"))
      (node (ref "U9") (pin "10") (pinfunction "S0_10") (pintype "input"))
    )
    (net (code "11") (name "/PA3_4052_S1_9") (class "Default")
      (node (ref "U2") (pin "13") (pinfunction "PA3_13") (pintype "input"))
      (node (ref "U9") (pin "9") (pinfunction "S1_9") (pintype "input"))
    )
    (net (code "12") (name "/PA4_U7_4053_6BEI") (class "Default")
      (node (ref "U2") (pin "14") (pinfunction "PA4_14") (pintype "input"))
      (node (ref "U7") (pin "9") (pinfunction "C_9") (pintype "input"))
    )
    (net (code "13") (name "/PA5_U7_4053_10BEI") (class "Default")
      (node (ref "U2") (pin "15") (pinfunction "PA5_15") (pintype "input"))
      (node (ref "U7") (pin "10") (pinfunction "B_10") (pintype "input"))
    )
    (net (code "14") (name "/PA6_U7_4053_3BEI") (class "Default")
      (node (ref "U2") (pin "16") (pinfunction "PA6_16") (pintype "input"))
      (node (ref "U7") (pin "11") (pinfunction "A_11") (pintype "input"))
    )
    (net (code "15") (name "/PA13_SWDIO") (class "Default")
      (node (ref "H3") (pin "3") (pinfunction "3_3") (pintype "input"))
      (node (ref "U2") (pin "34") (pinfunction "PA13_34") (pintype "input"))
    )
    (net (code "16") (name "/PA14_SWCLK") (class "Default")
      (node (ref "H3") (pin "2") (pinfunction "2_2") (pintype "input"))
      (node (ref "U2") (pin "37") (pinfunction "PA14_37") (pintype "input"))
    )
    (net (code "17") (name "/PA15_RST") (class "Default")
      (node (ref "U1") (pin "2") (pinfunction "RST_2") (pintype "input"))
      (node (ref "U2") (pin "38") (pinfunction "PA15_38") (pintype "input"))
    )
    (net (code "18") (name "/PB0_SHANGXIABI") (class "Default")
      (node (ref "U2") (pin "18") (pinfunction "PB0_18") (pintype "input"))
      (node (ref "U8") (pin "10") (pinfunction "B_10") (pintype "input"))
      (node (ref "U8") (pin "9") (pinfunction "C_9") (pintype "input"))
    )
    (net (code "19") (name "/PB3_SPI1_SCK") (class "Default")
      (node (ref "U1") (pin "4") (pinfunction "SCLK_4") (pintype "input"))
      (node (ref "U2") (pin "39") (pinfunction "PB3_39") (pintype "input"))
    )
    (net (code "20") (name "/PB4_RS") (class "Default")
      (node (ref "U1") (pin "3") (pinfunction "RS_3") (pintype "input"))
      (node (ref "U2") (pin "40") (pinfunction "PB4_40") (pintype "input"))
    )
    (net (code "21") (name "/PB5_SPI1_MOSI") (class "Default")
      (node (ref "U1") (pin "5") (pinfunction "SDA_5") (pintype "input"))
      (node (ref "U2") (pin "41") (pinfunction "PB5_41") (pintype "input"))
    )
    (net (code "22") (name "/PB8_GUANJI") (class "Default")
      (node (ref "R7") (pin "1") (pinfunction "1_1") (pintype "input"))
      (node (ref "U2") (pin "45") (pinfunction "PB8_45") (pintype "input"))
    )
    (net (code "23") (name "/PB9_LCD_BEIGUANG") (class "Default")
      (node (ref "R51") (pin "2") (pinfunction "2_2") (pintype "input"))
      (node (ref "U2") (pin "46") (pinfunction "PB9_46") (pintype "input"))
    )
    (net (code "24") (name "/PB12_KAIJI") (class "Default")
      (node (ref "D2") (pin "2") (pinfunction "A_2") (pintype "input"))
      (node (ref "R67") (pin "1") (pinfunction "1_1") (pintype "input"))
    )
    (net (code "25") (name "/SIN") (class "Default")
      (node (ref "C45") (pin "1") (pinfunction "1_1") (pintype "input"))
      (node (ref "C46") (pin "2") (pinfunction "2_2") (pintype "input"))
      (node (ref "C54") (pin "2") (pinfunction "2_2") (pintype "input"))
      (node (ref "R57") (pin "2") (pinfunction "2_2") (pintype "input"))
      (node (ref "R58") (pin "1") (pinfunction "1_1") (pintype "input"))
      (node (ref "R59") (pin "1") (pinfunction "1_1") (pintype "input"))
    )
    (net (code "26") (name "GND") (class "Default")
      (node (ref "C1") (pin "2") (pinfunction "2_2") (pintype "input"))
      (node (ref "C10") (pin "2") (pinfunction "2_2") (pintype "input"))
      (node (ref "C11") (pin "2") (pinfunction "2_2") (pintype "input"))
      (node (ref "C12") (pin "2") (pinfunction "2_2") (pintype "input"))
      (node (ref "C13") (pin "1") (pinfunction "1_1") (pintype "input"))
      (node (ref "C15") (pin "1") (pinfunction "1_1") (pintype "input"))
      (node (ref "C16") (pin "1") (pinfunction "1_1") (pintype "input"))
      (node (ref "C17") (pin "1") (pinfunction "1_1") (pintype "input"))
      (node (ref "C18") (pin "1") (pinfunction "1_1") (pintype "input"))
      (node (ref "C19") (pin "2") (pinfunction "2_2") (pintype "input"))
      (node (ref "C2") (pin "2") (pinfunction "2_2") (pintype "input"))
      (node (ref "C20") (pin "1") (pinfunction "1_1") (pintype "input"))
      (node (ref "C22") (pin "2") (pinfunction "2_2") (pintype "input"))
      (node (ref "C25") (pin "1") (pinfunction "1_1") (pintype "input"))
      (node (ref "C26") (pin "1") (pinfunction "1_1") (pintype "input"))
      (node (ref "C27") (pin "1") (pinfunction "1_1") (pintype "input"))
      (node (ref "C28") (pin "2") (pinfunction "2_2") (pintype "input"))
      (node (ref "C29") (pin "2") (pinfunction "2_2") (pintype "input"))
      (node (ref "C3") (pin "2") (pinfunction "2_2") (pintype "input"))
      (node (ref "C30") (pin "2") (pinfunction "2_2") (pintype "input"))
      (node (ref "C31") (pin "1") (pinfunction "1_1") (pintype "input"))
      (node (ref "C32") (pin "1") (pinfunction "1_1") (pintype "input"))
      (node (ref "C34") (pin "1") (pinfunction "1_1") (pintype "input"))
      (node (ref "C35") (pin "1") (pinfunction "1_1") (pintype "input"))
      (node (ref "C37") (pin "1") (pinfunction "1_1") (pintype "input"))
      (node (ref "C38") (pin "1") (pinfunction "1_1") (pintype "input"))
      (node (ref "C39") (pin "1") (pinfunction "1_1") (pintype "input"))
      (node (ref "C4") (pin "1") (pinfunction "1_1") (pintype "input"))
      (node (ref "C40") (pin "1") (pinfunction "1_1") (pintype "input"))
      (node (ref "C46") (pin "1") (pinfunction "1_1") (pintype "input"))
      (node (ref "C5") (pin "1") (pinfunction "1_1") (pintype "input"))
      (node (ref "C55") (pin "1") (pinfunction "1_1") (pintype "input"))
      (node (ref "C6") (pin "1") (pinfunction "1_1") (pintype "input"))
      (node (ref "C7") (pin "1") (pinfunction "1_1") (pintype "input"))
      (node (ref "C8") (pin "1") (pinfunction "1_1") (pintype "input"))
      (node (ref "C9") (pin "2") (pinfunction "2_2") (pintype "input"))
      (node (ref "H11") (pin "2") (pinfunction "2_2") (pintype "input"))
      (node (ref "H3") (pin "1") (pinfunction "1_1") (pintype "input"))
      (node (ref "LDO2") (pin "1") (pinfunction "GND_1") (pintype "input"))
      (node (ref "Q1") (pin "2") (pinfunction "S_2") (pintype "input"))
      (node (ref "R1") (pin "2") (pinfunction "2_2") (pintype "input"))
      (node (ref "R10") (pin "1") (pinfunction "1_1") (pintype "input"))
      (node (ref "R2") (pin "1") (pinfunction "1_1") (pintype "input"))
      (node (ref "R20") (pin "1") (pinfunction "1_1") (pintype "input"))
      (node (ref "R3") (pin "1") (pinfunction "1_1") (pintype "input"))
      (node (ref "R39") (pin "1") (pinfunction "1_1") (pintype "input"))
      (node (ref "R43") (pin "1") (pinfunction "1_1") (pintype "input"))
      (node (ref "R50") (pin "2") (pinfunction "2_2") (pintype "input"))
      (node (ref "R62") (pin "2") (pinfunction "2_2") (pintype "input"))
      (node (ref "R63") (pin "1") (pinfunction "1_1") (pintype "input"))
      (node (ref "SW1") (pin "3") (pinfunction "3_3") (pintype "input"))
      (node (ref "SW1") (pin "4") (pinfunction "4_4") (pintype "input"))
      (node (ref "SW2") (pin "3") (pinfunction "3_3") (pintype "input"))
      (node (ref "SW2") (pin "4") (pinfunction "4_4") (pintype "input"))
      (node (ref "SW3") (pin "3") (pinfunction "3_3") (pintype "input"))
      (node (ref "SW3") (pin "4") (pinfunction "4_4") (pintype "input"))
      (node (ref "SW4") (pin "3") (pinfunction "3_3") (pintype "input"))
      (node (ref "SW4") (pin "4") (pinfunction "4_4") (pintype "input"))
      (node (ref "U1") (pin "1") (pinfunction "CS_1") (pintype "input"))
      (node (ref "U1") (pin "7") (pinfunction "VSS_7") (pintype "input"))
      (node (ref "U10") (pin "1") (pinfunction "TEMP_1") (pintype "input"))
      (node (ref "U10") (pin "3") (pinfunction "GND_3") (pintype "input"))
      (node (ref "U11") (pin "4") (pinfunction "-VS_4") (pintype "input"))
      (node (ref "U2") (pin "23") (pinfunction "VSS_23") (pintype "input"))
      (node (ref "U2") (pin "47") (pinfunction "VSS_47") (pintype "input"))
      (node (ref "U2") (pin "8") (pinfunction "VSSA_8") (pintype "input"))
      (node (ref "U3") (pin "4") (pinfunction "-VS_4") (pintype "input"))
      (node (ref "U4") (pin "4") (pinfunction "-VS_4") (pintype "input"))
      (node (ref "U5") (pin "4") (pinfunction "-VS_4") (pintype "input"))
      (node (ref "U6") (pin "4") (pinfunction "-VS_4") (pintype "input"))
      (node (ref "U7") (pin "6") (pinfunction "ENABLE#_6") (pintype "input"))
      (node (ref "U7") (pin "7") (pinfunction "NC_7") (pintype "input"))
      (node (ref "U7") (pin "8") (pinfunction "GND_8") (pintype "input"))
      (node (ref "U8") (pin "6") (pinfunction "ENABLE#_6") (pintype "input"))
      (node (ref "U8") (pin "7") (pinfunction "NC_7") (pintype "input"))
      (node (ref "U8") (pin "8") (pinfunction "GND_8") (pintype "input"))
      (node (ref "U9") (pin "6") (pinfunction "E#_6") (pintype "input"))
      (node (ref "U9") (pin "7") (pinfunction "VEE_7") (pintype "input"))
      (node (ref "U9") (pin "8") (pinfunction "GND_8") (pintype "input"))
      (node (ref "USB1") (pin "A1B12") (pinfunction "GND_A1B12") (pintype "input"))
      (node (ref "USB1") (pin "B1A12") (pinfunction "GND_B1A12") (pintype "input"))
      (node (ref "USB1") (pin "EP") (pinfunction "EP_EP") (pintype "input"))
    )
    (net (code "27") (name "Net-(C37-Pad2)") (class "Default")
      (node (ref "C37") (pin "2") (pinfunction "2_2") (pintype "input"))
      (node (ref "C41") (pin "1") (pinfunction "1_1") (pintype "input"))
      (node (ref "R53") (pin "2") (pinfunction "2_2") (pintype "input"))
      (node (ref "R54") (pin "1") (pinfunction "1_1") (pintype "input"))
    )
    (net (code "28") (name "Net-(C38-Pad2)") (class "Default")
      (node (ref "C38") (pin "2") (pinfunction "2_2") (pintype "input"))
      (node (ref "C42") (pin "1") (pinfunction "1_1") (pintype "input"))
      (node (ref "R54") (pin "2") (pinfunction "2_2") (pintype "input"))
      (node (ref "R55") (pin "1") (pinfunction "1_1") (pintype "input"))
    )
    (net (code "29") (name "Net-(C39-Pad2)") (class "Default")
      (node (ref "C39") (pin "2") (pinfunction "2_2") (pintype "input"))
      (node (ref "C43") (pin "1") (pinfunction "1_1") (pintype "input"))
      (node (ref "R55") (pin "2") (pinfunction "2_2") (pintype "input"))
      (node (ref "R56") (pin "1") (pinfunction "1_1") (pintype "input"))
    )
    (net (code "30") (name "Net-(C40-Pad2)") (class "Default")
      (node (ref "C40") (pin "2") (pinfunction "2_2") (pintype "input"))
      (node (ref "C44") (pin "1") (pinfunction "1_1") (pintype "input"))
      (node (ref "R56") (pin "2") (pinfunction "2_2") (pintype "input"))
      (node (ref "R57") (pin "1") (pinfunction "1_1") (pintype "input"))
    )
    (net (code "31") (name "Net-(C49-Pad2)") (class "Default")
      (node (ref "C49") (pin "2") (pinfunction "2_2") (pintype "input"))
      (node (ref "R37") (pin "1") (pinfunction "1_1") (pintype "input"))
      (node (ref "R39") (pin "2") (pinfunction "2_2") (pintype "input"))
    )
    (net (code "32") (name "Net-(C50-Pad2)") (class "Default")
      (node (ref "C50") (pin "2") (pinfunction "2_2") (pintype "input"))
      (node (ref "R49") (pin "1") (pinfunction "1_1") (pintype "input"))
      (node (ref "R50") (pin "1") (pinfunction "1_1") (pintype "input"))
    )
    (net (code "33") (name "Net-(C51-Pad1)") (class "Default")
      (node (ref "C51") (pin "1") (pinfunction "1_1") (pintype "input"))
      (node (ref "R41") (pin "1") (pinfunction "1_1") (pintype "input"))
      (node (ref "R43") (pin "2") (pinfunction "2_2") (pintype "input"))
    )
    (net (code "34") (name "Net-(D1-A)") (class "Default")
      (node (ref "D1") (pin "2") (pinfunction "A_2") (pintype "input"))
      (node (ref "Q1") (pin "3") (pinfunction "D_3") (pintype "input"))
      (node (ref "Q2") (pin "1") (pinfunction "G_1") (pintype "input"))
      (node (ref "R6") (pin "1") (pinfunction "1_1") (pintype "input"))
    )
    (net (code "35") (name "Net-(D1-C)") (class "Default")
      (node (ref "D1") (pin "1") (pinfunction "C_1") (pintype "input"))
      (node (ref "D2") (pin "1") (pinfunction "C_1") (pintype "input"))
      (node (ref "SW4") (pin "1") (pinfunction "1_1") (pintype "input"))
      (node (ref "SW4") (pin "2") (pinfunction "2_2") (pintype "input"))
    )
    (net (code "36") (name "Net-(LDO2-VDD)") (class "Default")
      (node (ref "C6") (pin "2") (pinfunction "2_2") (pintype "input"))
      (node (ref "LDO2") (pin "3") (pinfunction "VDD_3") (pintype "input"))
      (node (ref "Q2") (pin "3") (pinfunction "D_3") (pintype "input"))
    )
    (net (code "37") (name "Net-(LED1-A)") (class "Default")
      (node (ref "LED1") (pin "2") (pinfunction "A_2") (pintype "input"))
      (node (ref "R4") (pin "2") (pinfunction "2_2") (pintype "input"))
    )
    (net (code "38") (name "Net-(LED2-A)") (class "Default")
      (node (ref "LED2") (pin "2") (pinfunction "A_2") (pintype "input"))
      (node (ref "R5") (pin "2") (pinfunction "2_2") (pintype "input"))
    )
    (net (code "39") (name "Net-(LED3-A)") (class "Default")
      (node (ref "LED3") (pin "2") (pinfunction "A_2") (pintype "input"))
      (node (ref "R51") (pin "1") (pinfunction "1_1") (pintype "input"))
    )
    (net (code "40") (name "Net-(Q1-G)") (class "Default")
      (node (ref "Q1") (pin "1") (pinfunction "G_1") (pintype "input"))
      (node (ref "R7") (pin "2") (pinfunction "2_2") (pintype "input"))
    )
    (net (code "41") (name "Net-(R64-Pad1)") (class "Default")
      (node (ref "R64") (pin "1") (pinfunction "1_1") (pintype "input"))
      (node (ref "SW3") (pin "1") (pinfunction "1_1") (pintype "input"))
      (node (ref "SW3") (pin "2") (pinfunction "2_2") (pintype "input"))
    )
    (net (code "42") (name "Net-(R65-Pad1)") (class "Default")
      (node (ref "R65") (pin "1") (pinfunction "1_1") (pintype "input"))
      (node (ref "SW2") (pin "1") (pinfunction "1_1") (pintype "input"))
      (node (ref "SW2") (pin "2") (pinfunction "2_2") (pintype "input"))
    )
    (net (code "43") (name "Net-(R66-Pad1)") (class "Default")
      (node (ref "R66") (pin "1") (pinfunction "1_1") (pintype "input"))
      (node (ref "SW1") (pin "1") (pinfunction "1_1") (pintype "input"))
      (node (ref "SW1") (pin "2") (pinfunction "2_2") (pintype "input"))
    )
    (net (code "44") (name "Net-(U1-V0)") (class "Default")
      (node (ref "C33") (pin "2") (pinfunction "2_2") (pintype "input"))
      (node (ref "U1") (pin "8") (pinfunction "V0_8") (pintype "input"))
    )
    (net (code "45") (name "Net-(U1-VG)") (class "Default")
      (node (ref "C34") (pin "2") (pinfunction "2_2") (pintype "input"))
      (node (ref "U1") (pin "10") (pinfunction "VG_10") (pintype "input"))
    )
    (net (code "46") (name "Net-(U1-XV0)") (class "Default")
      (node (ref "C33") (pin "1") (pinfunction "1_1") (pintype "input"))
      (node (ref "U1") (pin "9") (pinfunction "XV0_9") (pintype "input"))
    )
    (net (code "47") (name "Net-(U2-NRST)") (class "Default")
      (node (ref "C28") (pin "1") (pinfunction "1_1") (pintype "input"))
      (node (ref "U2") (pin "7") (pinfunction "NRST_7") (pintype "input"))
    )
    (net (code "48") (name "Net-(U2-PA1)") (class "Default")
      (node (ref "R60") (pin "2") (pinfunction "2_2") (pintype "input"))
      (node (ref "U2") (pin "11") (pinfunction "PA1_11") (pintype "input"))
    )
    (net (code "49") (name "Net-(U2-PA8)") (class "Default")
      (node (ref "R53") (pin "1") (pinfunction "1_1") (pintype "input"))
      (node (ref "U2") (pin "29") (pinfunction "PA8_29") (pintype "input"))
    )
    (net (code "50") (name "Net-(U2-PA9)") (class "Default")
      (node (ref "C41") (pin "2") (pinfunction "2_2") (pintype "input"))
      (node (ref "U2") (pin "30") (pinfunction "PA9_30") (pintype "input"))
    )
    (net (code "51") (name "Net-(U2-PA10)") (class "Default")
      (node (ref "C42") (pin "2") (pinfunction "2_2") (pintype "input"))
      (node (ref "U2") (pin "31") (pinfunction "PA10_31") (pintype "input"))
    )
    (net (code "52") (name "Net-(U2-PA11)") (class "Default")
      (node (ref "C43") (pin "2") (pinfunction "2_2") (pintype "input"))
      (node (ref "U2") (pin "32") (pinfunction "PA11_32") (pintype "input"))
    )
    (net (code "53") (name "Net-(U2-PA12)") (class "Default")
      (node (ref "C44") (pin "2") (pinfunction "2_2") (pintype "input"))
      (node (ref "U2") (pin "33") (pinfunction "PA12_33") (pintype "input"))
    )
    (net (code "54") (name "Net-(U2-PB1)") (class "Default")
      (node (ref "H8") (pin "1") (pinfunction "1_1") (pintype "unspecified"))
      (node (ref "U2") (pin "19") (pinfunction "PB1_19") (pintype "input"))
    )
    (net (code "55") (name "Net-(U2-PB6)") (class "Default")
      (node (ref "R59") (pin "2") (pinfunction "2_2") (pintype "input"))
      (node (ref "U2") (pin "42") (pinfunction "PB6_42") (pintype "input"))
    )
    (net (code "56") (name "Net-(U2-PB7)") (class "Default")
      (node (ref "H10") (pin "1") (pinfunction "1_1") (pintype "unspecified"))
      (node (ref "U2") (pin "43") (pinfunction "PB7_43") (pintype "input"))
    )
    (net (code "57") (name "Net-(U2-PB10)") (class "Default")
      (node (ref "C47") (pin "1") (pinfunction "1_1") (pintype "input"))
      (node (ref "U2") (pin "21") (pinfunction "PB10_21") (pintype "input"))
    )
    (net (code "58") (name "Net-(U2-PB11)") (class "Default")
      (node (ref "C48") (pin "1") (pinfunction "1_1") (pintype "input"))
      (node (ref "U2") (pin "22") (pinfunction "PB11_22") (pintype "input"))
    )
    (net (code "59") (name "Net-(U2-PB12)") (class "Default")
      (node (ref "R67") (pin "2") (pinfunction "2_2") (pintype "input"))
      (node (ref "U2") (pin "25") (pinfunction "PB12_25") (pintype "input"))
    )
    (net (code "60") (name "Net-(U2-PB13)") (class "Default")
      (node (ref "R66") (pin "2") (pinfunction "2_2") (pintype "input"))
      (node (ref "U2") (pin "26") (pinfunction "PB13_26") (pintype "input"))
    )
    (net (code "61") (name "Net-(U2-PB14)") (class "Default")
      (node (ref "R65") (pin "2") (pinfunction "2_2") (pintype "input"))
      (node (ref "U2") (pin "27") (pinfunction "PB14_27") (pintype "input"))
    )
    (net (code "62") (name "Net-(U2-PB15)") (class "Default")
      (node (ref "R64") (pin "2") (pinfunction "2_2") (pintype "input"))
      (node (ref "U2") (pin "28") (pinfunction "PB15_28") (pintype "input"))
    )
    (net (code "63") (name "Net-(U2-PC13-TAMPER-RTC)") (class "Default")
      (node (ref "H7") (pin "1") (pinfunction "1_1") (pintype "unspecified"))
      (node (ref "U2") (pin "2") (pinfunction "PC13-TAMPER-RTC_2") (pintype "input"))
    )
    (net (code "64") (name "Net-(U2-PC14-OSC32_IN)") (class "Default")
      (node (ref "H6") (pin "1") (pinfunction "1_1") (pintype "unspecified"))
      (node (ref "U2") (pin "3") (pinfunction "PC14-OSC32_IN_3") (pintype "input"))
    )
    (net (code "65") (name "Net-(U2-PC15-OSC32_OUT)") (class "Default")
      (node (ref "H5") (pin "1") (pinfunction "1_1") (pintype "unspecified"))
      (node (ref "U2") (pin "4") (pinfunction "PC15-OSC32_OUT_4") (pintype "input"))
    )
    (net (code "66") (name "Net-(U2-PD0-BOOT0)") (class "Default")
      (node (ref "R63") (pin "2") (pinfunction "2_2") (pintype "input"))
      (node (ref "U2") (pin "44") (pinfunction "PD0-BOOT0_44") (pintype "input"))
    )
    (net (code "67") (name "Net-(U2-PD12)") (class "Default")
      (node (ref "C45") (pin "2") (pinfunction "2_2") (pintype "input"))
      (node (ref "U2") (pin "35") (pinfunction "PD12_35") (pintype "input"))
    )
    (net (code "68") (name "Net-(U2-PD13)") (class "Default")
      (node (ref "R58") (pin "2") (pinfunction "2_2") (pintype "input"))
      (node (ref "U2") (pin "36") (pinfunction "PD13_36") (pintype "input"))
    )
    (net (code "69") (name "Net-(U2-PD14-OSC_IN)") (class "Default")
      (node (ref "C26") (pin "2") (pinfunction "2_2") (pintype "input"))
      (node (ref "U2") (pin "5") (pinfunction "PD14-OSC_IN_5") (pintype "input"))
      (node (ref "X1") (pin "1") (pinfunction "OSC1_1") (pintype "input"))
    )
    (net (code "70") (name "Net-(U2-PD15-OSC_OUT)") (class "Default")
      (node (ref "C27") (pin "2") (pinfunction "2_2") (pintype "input"))
      (node (ref "U2") (pin "6") (pinfunction "PD15-OSC_OUT_6") (pintype "input"))
      (node (ref "X1") (pin "2") (pinfunction "OSC2_2") (pintype "input"))
    )
    (net (code "71") (name "Net-(U3-+IN1)") (class "Default")
      (node (ref "C13") (pin "2") (pinfunction "2_2") (pintype "input"))
      (node (ref "R10") (pin "2") (pinfunction "2_2") (pintype "input"))
      (node (ref "R9") (pin "1") (pinfunction "1_1") (pintype "input"))
      (node (ref "U3") (pin "3") (pinfunction "+IN1_3") (pintype "input"))
    )
    (net (code "72") (name "Net-(U3-+IN2)") (class "Default")
      (node (ref "C54") (pin "1") (pinfunction "1_1") (pintype "input"))
      (node (ref "R72") (pin "2") (pinfunction "2_2") (pintype "input"))
      (node (ref "U3") (pin "5") (pinfunction "+IN2_5") (pintype "input"))
    )
    (net (code "73") (name "Net-(U3--IN1)") (class "Default")
      (node (ref "R77") (pin "2") (pinfunction "2_2") (pintype "input"))
      (node (ref "U3") (pin "1") (pinfunction "OUTA_1") (pintype "input"))
      (node (ref "U3") (pin "2") (pinfunction "-IN1_2") (pintype "input"))
    )
    (net (code "74") (name "Net-(U3--IN2)") (class "Default")
      (node (ref "R12") (pin "2") (pinfunction "2_2") (pintype "input"))
      (node (ref "U3") (pin "6") (pinfunction "-IN2_6") (pintype "input"))
      (node (ref "U3") (pin "7") (pinfunction "OUTB_7") (pintype "input"))
    )
    (net (code "75") (name "Net-(U4-+IN2)") (class "Default")
      (node (ref "C15") (pin "2") (pinfunction "2_2") (pintype "input"))
      (node (ref "R19") (pin "1") (pinfunction "1_1") (pintype "input"))
      (node (ref "R20") (pin "2") (pinfunction "2_2") (pintype "input"))
      (node (ref "U4") (pin "5") (pinfunction "+IN2_5") (pintype "input"))
    )
    (net (code "76") (name "Net-(U4--IN1)") (class "Default")
      (node (ref "C36") (pin "1") (pinfunction "1_1") (pintype "input"))
      (node (ref "R52") (pin "2") (pinfunction "2_2") (pintype "input"))
      (node (ref "U4") (pin "2") (pinfunction "-IN1_2") (pintype "input"))
    )
    (net (code "77") (name "Net-(U4-OUTA)") (class "Default")
      (node (ref "C36") (pin "2") (pinfunction "2_2") (pintype "input"))
      (node (ref "U4") (pin "1") (pinfunction "OUTA_1") (pintype "input"))
      (node (ref "U9") (pin "3") (pinfunction "2Z_3") (pintype "input"))
    )
    (net (code "78") (name "Net-(U4-OUTB)") (class "Default")
      (node (ref "R21") (pin "2") (pinfunction "2_2") (pintype "input"))
      (node (ref "U4") (pin "7") (pinfunction "OUTB_7") (pintype "input"))
    )
    (net (code "79") (name "Net-(U5-+IN1)") (class "Default")
      (node (ref "R75") (pin "2") (pinfunction "2_2") (pintype "input"))
      (node (ref "R8") (pin "1") (pinfunction "1_1") (pintype "input"))
      (node (ref "U5") (pin "3") (pinfunction "+IN1_3") (pintype "input"))
    )
    (net (code "80") (name "Net-(U5-+IN2)") (class "Default")
      (node (ref "R22") (pin "1") (pinfunction "1_1") (pintype "input"))
      (node (ref "R76") (pin "2") (pinfunction "2_2") (pintype "input"))
      (node (ref "U5") (pin "5") (pinfunction "+IN2_5") (pintype "input"))
    )
    (net (code "81") (name "Net-(U5--IN1)") (class "Default")
      (node (ref "R40") (pin "1") (pinfunction "1_1") (pintype "input"))
      (node (ref "R42") (pin "2") (pinfunction "2_2") (pintype "input"))
      (node (ref "U5") (pin "2") (pinfunction "-IN1_2") (pintype "input"))
    )
    (net (code "82") (name "Net-(U5--IN2)") (class "Default")
      (node (ref "R47") (pin "1") (pinfunction "1_1") (pintype "input"))
      (node (ref "R48") (pin "2") (pinfunction "2_2") (pintype "input"))
      (node (ref "U5") (pin "6") (pinfunction "-IN2_6") (pintype "input"))
    )
    (net (code "83") (name "Net-(U5-OUTA)") (class "Default")
      (node (ref "R40") (pin "2") (pinfunction "2_2") (pintype "input"))
      (node (ref "R41") (pin "2") (pinfunction "2_2") (pintype "input"))
      (node (ref "U5") (pin "1") (pinfunction "OUTA_1") (pintype "input"))
      (node (ref "U7") (pin "13") (pinfunction "X1_13") (pintype "input"))
    )
    (net (code "84") (name "Net-(U5-OUTB)") (class "Default")
      (node (ref "R46") (pin "1") (pinfunction "1_1") (pintype "input"))
      (node (ref "R47") (pin "2") (pinfunction "2_2") (pintype "input"))
      (node (ref "U5") (pin "7") (pinfunction "OUTB_7") (pintype "input"))
    )
    (net (code "85") (name "Net-(U6-+IN1)") (class "Default")
      (node (ref "R31") (pin "2") (pinfunction "2_2") (pintype "input"))
      (node (ref "R33") (pin "2") (pinfunction "2_2") (pintype "input"))
      (node (ref "U6") (pin "3") (pinfunction "+IN1_3") (pintype "input"))
    )
    (net (code "86") (name "Net-(U6-+IN2)") (class "Default")
      (node (ref "R73") (pin "1") (pinfunction "1_1") (pintype "input"))
      (node (ref "R74") (pin "2") (pinfunction "2_2") (pintype "input"))
      (node (ref "U6") (pin "5") (pinfunction "+IN2_5") (pintype "input"))
    )
    (net (code "87") (name "Net-(U6--IN1)") (class "Default")
      (node (ref "R30") (pin "2") (pinfunction "2_2") (pintype "input"))
      (node (ref "R32") (pin "2") (pinfunction "2_2") (pintype "input"))
      (node (ref "U6") (pin "2") (pinfunction "-IN1_2") (pintype "input"))
    )
    (net (code "88") (name "Net-(U6--IN2)") (class "Default")
      (node (ref "R35") (pin "1") (pinfunction "1_1") (pintype "input"))
      (node (ref "R38") (pin "2") (pinfunction "2_2") (pintype "input"))
      (node (ref "U6") (pin "6") (pinfunction "-IN2_6") (pintype "input"))
    )
    (net (code "89") (name "Net-(U6-OUTA)") (class "Default")
      (node (ref "R30") (pin "1") (pinfunction "1_1") (pintype "input"))
      (node (ref "R49") (pin "2") (pinfunction "2_2") (pintype "input"))
      (node (ref "U6") (pin "1") (pinfunction "OUTA_1") (pintype "input"))
      (node (ref "U7") (pin "5") (pinfunction "Z0_5") (pintype "input"))
    )
    (net (code "90") (name "Net-(U6-OUTB)") (class "Default")
      (node (ref "R35") (pin "2") (pinfunction "2_2") (pintype "input"))
      (node (ref "R37") (pin "2") (pinfunction "2_2") (pintype "input"))
      (node (ref "U6") (pin "7") (pinfunction "OUTB_7") (pintype "input"))
      (node (ref "U7") (pin "1") (pinfunction "Y1_1") (pintype "input"))
    )
    (net (code "91") (name "Net-(U7-X)") (class "Default")
      (node (ref "R76") (pin "1") (pinfunction "1_1") (pintype "input"))
      (node (ref "U7") (pin "14") (pinfunction "X_14") (pintype "input"))
    )
    (net (code "92") (name "Net-(U7-X0)") (class "Default")
      (node (ref "C51") (pin "2") (pinfunction "2_2") (pintype "input"))
      (node (ref "R71") (pin "1") (pinfunction "1_1") (pintype "input"))
      (node (ref "U7") (pin "12") (pinfunction "X0_12") (pintype "input"))
    )
    (net (code "93") (name "Net-(U7-Y)") (class "Default")
      (node (ref "R75") (pin "1") (pinfunction "1_1") (pintype "input"))
      (node (ref "U7") (pin "15") (pinfunction "Y_15") (pintype "input"))
    )
    (net (code "94") (name "Net-(U7-Y0)") (class "Default")
      (node (ref "C49") (pin "1") (pinfunction "1_1") (pintype "input"))
      (node (ref "R69") (pin "2") (pinfunction "2_2") (pintype "input"))
      (node (ref "U7") (pin "2") (pinfunction "Y0_2") (pintype "input"))
    )
    (net (code "95") (name "Net-(U7-Z)") (class "Default")
      (node (ref "R74") (pin "1") (pinfunction "1_1") (pintype "input"))
      (node (ref "U7") (pin "4") (pinfunction "Z_4") (pintype "input"))
    )
    (net (code "96") (name "Net-(U7-Z1)") (class "Default")
      (node (ref "C50") (pin "1") (pinfunction "1_1") (pintype "input"))
      (node (ref "R70") (pin "2") (pinfunction "2_2") (pintype "input"))
      (node (ref "U7") (pin "3") (pinfunction "Z1_3") (pintype "input"))
    )
    (net (code "97") (name "Net-(U8-Y0)") (class "Default")
      (node (ref "R28") (pin "2") (pinfunction "2_2") (pintype "input"))
      (node (ref "U8") (pin "2") (pinfunction "Y0_2") (pintype "input"))
    )
    (net (code "98") (name "Net-(U8-Y1)") (class "Default")
      (node (ref "R26") (pin "2") (pinfunction "2_2") (pintype "input"))
      (node (ref "U8") (pin "1") (pinfunction "Y1_1") (pintype "input"))
    )
    (net (code "99") (name "Net-(U8-Z0)") (class "Default")
      (node (ref "R29") (pin "2") (pinfunction "2_2") (pintype "input"))
      (node (ref "U8") (pin "5") (pinfunction "Z0_5") (pintype "input"))
    )
    (net (code "100") (name "Net-(U8-Z1)") (class "Default")
      (node (ref "R27") (pin "2") (pinfunction "2_2") (pintype "input"))
      (node (ref "U8") (pin "3") (pinfunction "Z1_3") (pintype "input"))
    )
    (net (code "101") (name "Net-(U9-1Y0)") (class "Default")
      (node (ref "R18") (pin "1") (pinfunction "1_1") (pintype "input"))
      (node (ref "U9") (pin "1") (pinfunction "2Y0_1") (pintype "input"))
      (node (ref "U9") (pin "12") (pinfunction "1Y0_12") (pintype "input"))
    )
    (net (code "102") (name "Net-(U9-1Y1)") (class "Default")
      (node (ref "R17") (pin "1") (pinfunction "1_1") (pintype "input"))
      (node (ref "U9") (pin "14") (pinfunction "1Y1_14") (pintype "input"))
      (node (ref "U9") (pin "5") (pinfunction "2Y1_5") (pintype "input"))
    )
    (net (code "103") (name "Net-(U9-1Y2)") (class "Default")
      (node (ref "R16") (pin "1") (pinfunction "1_1") (pintype "input"))
      (node (ref "U9") (pin "15") (pinfunction "1Y2_15") (pintype "input"))
      (node (ref "U9") (pin "2") (pinfunction "2Y2_2") (pintype "input"))
    )
    (net (code "104") (name "Net-(U9-1Y3)") (class "Default")
      (node (ref "R15") (pin "1") (pinfunction "1_1") (pintype "input"))
      (node (ref "U9") (pin "11") (pinfunction "1Y3_11") (pintype "input"))
      (node (ref "U9") (pin "4") (pinfunction "2Y3_4") (pintype "input"))
    )
    (net (code "105") (name "Net-(U9-1Z)") (class "Default")
      (node (ref "R26") (pin "1") (pinfunction "1_1") (pintype "input"))
      (node (ref "U9") (pin "13") (pinfunction "1Z_13") (pintype "input"))
    )
    (net (code "106") (name "Net-(U10-CHRG#)") (class "Default")
      (node (ref "R4") (pin "1") (pinfunction "1_1") (pintype "input"))
      (node (ref "U10") (pin "7") (pinfunction "CHRG#_7") (pintype "input"))
    )
    (net (code "107") (name "Net-(U10-PROG)") (class "Default")
      (node (ref "R3") (pin "2") (pinfunction "2_2") (pintype "input"))
      (node (ref "U10") (pin "2") (pinfunction "PROG_2") (pintype "input"))
    )
    (net (code "108") (name "Net-(U10-STDBY#)") (class "Default")
      (node (ref "R5") (pin "1") (pinfunction "1_1") (pintype "input"))
      (node (ref "U10") (pin "6") (pinfunction "STDBY#_6") (pintype "input"))
    )
    (net (code "109") (name "Net-(U11-+IN1)") (class "Default")
      (node (ref "U11") (pin "3") (pinfunction "+IN1_3") (pintype "input"))
      (node (ref "U8") (pin "15") (pinfunction "Y_15") (pintype "input"))
    )
    (net (code "110") (name "Net-(U11-+IN2)") (class "Default")
      (node (ref "U11") (pin "5") (pinfunction "+IN2_5") (pintype "input"))
      (node (ref "U8") (pin "4") (pinfunction "Z_4") (pintype "input"))
    )
    (net (code "111") (name "Net-(U11--IN1)") (class "Default")
      (node (ref "R33") (pin "1") (pinfunction "1_1") (pintype "input"))
      (node (ref "U11") (pin "1") (pinfunction "OUTA_1") (pintype "input"))
      (node (ref "U11") (pin "2") (pinfunction "-IN1_2") (pintype "input"))
    )
    (net (code "112") (name "Net-(U11--IN2)") (class "Default")
      (node (ref "R32") (pin "1") (pinfunction "1_1") (pintype "input"))
      (node (ref "U11") (pin "6") (pinfunction "-IN2_6") (pintype "input"))
      (node (ref "U11") (pin "7") (pinfunction "OUTB_7") (pintype "input"))
    )
    (net (code "113") (name "Net-(USB1-CC1)") (class "Default")
      (node (ref "R1") (pin "1") (pinfunction "1_1") (pintype "input"))
      (node (ref "USB1") (pin "A5") (pinfunction "CC1_A5") (pintype "input"))
    )
    (net (code "114") (name "Net-(USB1-CC2)") (class "Default")
      (node (ref "R2") (pin "2") (pinfunction "2_2") (pintype "input"))
      (node (ref "USB1") (pin "B5") (pinfunction "CC2_B5") (pintype "input"))
    )
    (net (code "115") (name "VCC") (class "Default")
      (node (ref "C4") (pin "2") (pinfunction "2_2") (pintype "input"))
      (node (ref "LED1") (pin "1") (pinfunction "C_1") (pintype "input"))
      (node (ref "LED2") (pin "1") (pinfunction "C_1") (pintype "input"))
      (node (ref "U10") (pin "4") (pinfunction "Vcc_4") (pintype "input"))
      (node (ref "U10") (pin "8") (pinfunction "CE_8") (pintype "input"))
      (node (ref "USB1") (pin "A4B9") (pinfunction "VBUS_A4B9") (pintype "input"))
      (node (ref "USB1") (pin "B4A9") (pinfunction "VBUS_B4A9") (pintype "input"))
    )
    (net (code "116") (name "unconnected-(U2-PA7-Pad17)") (class "Default")
      (node (ref "U2") (pin "17") (pinfunction "PA7_17") (pintype "input"))
    )
    (net (code "117") (name "unconnected-(U8-A-Pad11)") (class "Default")
      (node (ref "U8") (pin "11") (pinfunction "A_11") (pintype "input"))
    )
    (net (code "118") (name "unconnected-(U8-X-Pad14)") (class "Default")
      (node (ref "U8") (pin "14") (pinfunction "X_14") (pintype "input"))
    )
    (net (code "119") (name "unconnected-(U8-X0-Pad12)") (class "Default")
      (node (ref "U8") (pin "12") (pinfunction "X0_12") (pintype "input"))
    )
    (net (code "120") (name "unconnected-(U8-X1-Pad13)") (class "Default")
      (node (ref "U8") (pin "13") (pinfunction "X1_13") (pintype "input"))
    )
    (net (code "121") (name "unconnected-(USB1-DN1-PadA7)") (class "Default")
      (node (ref "USB1") (pin "A7") (pinfunction "DN1_A7") (pintype "input+no_connect"))
    )
    (net (code "122") (name "unconnected-(USB1-DN2-PadB7)") (class "Default")
      (node (ref "USB1") (pin "B7") (pinfunction "DN2_B7") (pintype "input+no_connect"))
    )
    (net (code "123") (name "unconnected-(USB1-DP1-PadA6)") (class "Default")
      (node (ref "USB1") (pin "A6") (pinfunction "DP1_A6") (pintype "input+no_connect"))
    )
    (net (code "124") (name "unconnected-(USB1-DP2-PadB6)") (class "Default")
      (node (ref "USB1") (pin "B6") (pinfunction "DP2_B6") (pintype "input+no_connect"))
    )
    (net (code "125") (name "unconnected-(USB1-SBU1-PadA8)") (class "Default")
      (node (ref "USB1") (pin "A8") (pinfunction "SBU1_A8") (pintype "input+no_connect"))
    )
    (net (code "126") (name "unconnected-(USB1-SBU2-PadB8)") (class "Default")
      (node (ref "USB1") (pin "B8") (pinfunction "SBU2_B8") (pintype "input+no_connect"))
    )
  )
)
